# GPS_Tracker_v1_2.net
KiCad netlist of a schematic drawn in EAGLE
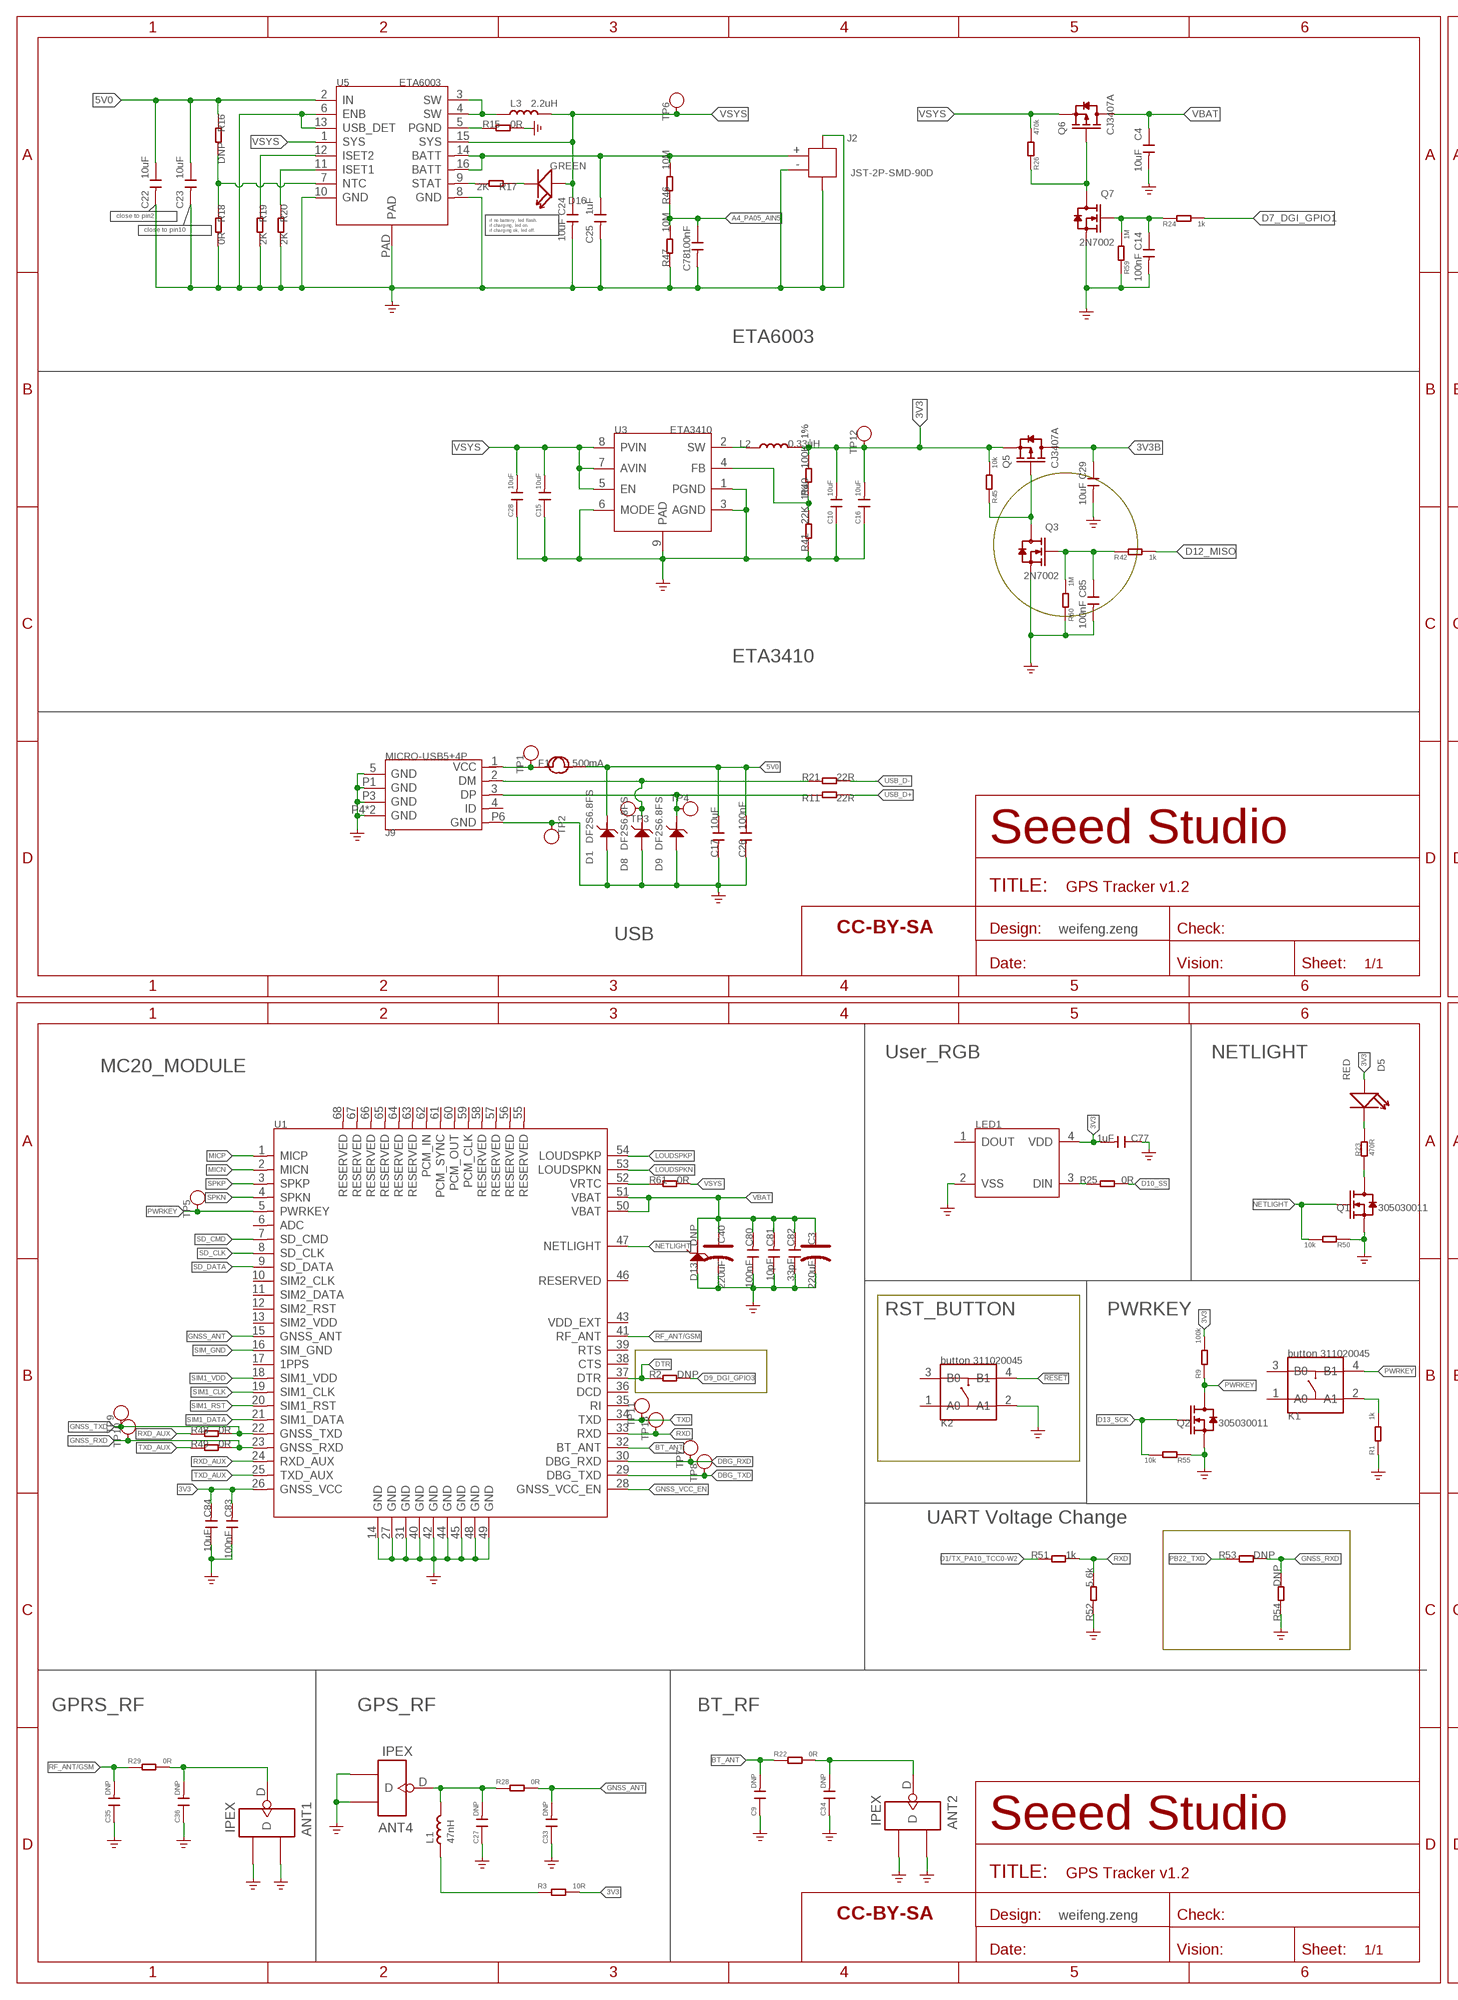
[diagram p0: schematic, sheet 1, part 1 of 2]
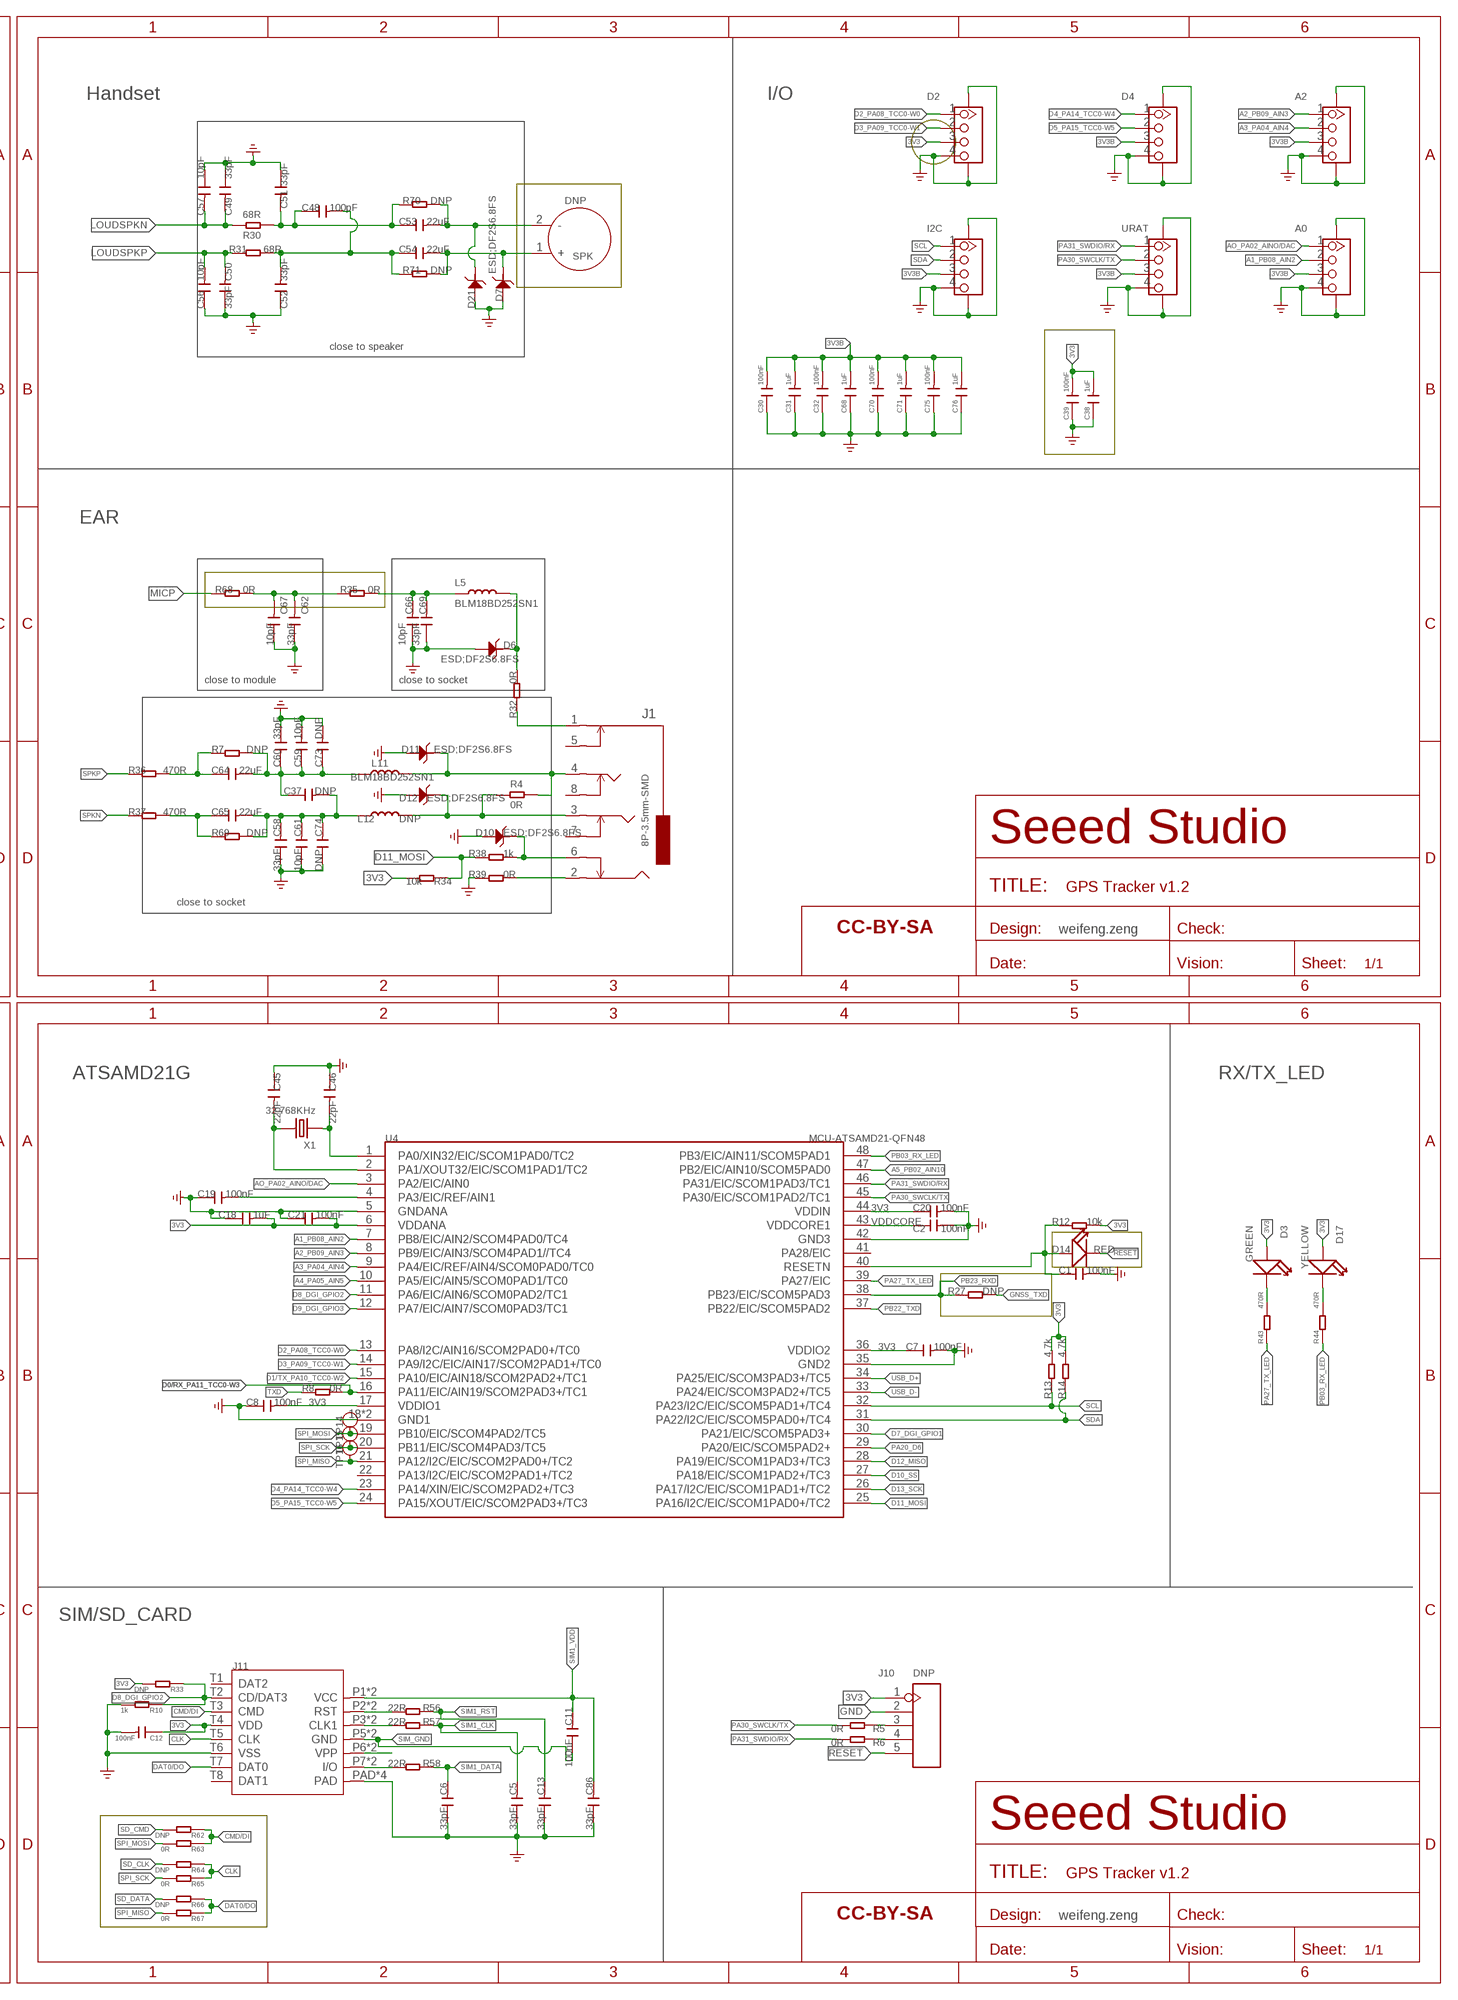
[diagram p1: schematic, sheet 1, part 2 of 2]

(export (version "E")
  (design (tool "Eeschema 10.0.6"))
  (components
    (comp (ref "A0")
      (value "GROVE-CONNECTOR-SMD'90D'")
      (footprint "eagle-import:HW4-SMD-2.0-90D")
      (libsource (lib "eagle-import") (part "GROVE-CONNECTOR-SMD'90D'"))
    )
    (comp (ref "A2")
      (value "GROVE-CONNECTOR-SMD'90D'")
      (footprint "eagle-import:HW4-SMD-2.0-90D")
      (libsource (lib "eagle-import") (part "GROVE-CONNECTOR-SMD'90D'"))
    )
    (comp (ref "ANT1")
      (value "IPEX")
      (footprint "eagle-import:U-FL3P-SMD-2.6X2.6X1.0MM")
      (libsource (lib "eagle-import") (part "ANTENNA-U-FL"))
    )
    (comp (ref "ANT2")
      (value "IPEX")
      (footprint "eagle-import:U-FL3P-SMD-2.6X2.6X1.0MM")
      (libsource (lib "eagle-import") (part "ANTENNA-U-FL"))
    )
    (comp (ref "ANT4")
      (value "IPEX")
      (footprint "eagle-import:U-FL3P-SMD-2.6X2.6X1.0MM")
      (libsource (lib "eagle-import") (part "ANTENNA-U-FL"))
    )
    (comp (ref "C1")
      (value "100nF")
      (footprint "eagle-import:C0402")
      (libsource (lib "eagle-import") (part "C-0402"))
    )
    (comp (ref "C2")
      (value "100nF")
      (footprint "eagle-import:C0402")
      (libsource (lib "eagle-import") (part "C-0402"))
    )
    (comp (ref "C3")
      (value "220uF")
      (footprint "eagle-import:AVX-B")
      (libsource (lib "eagle-import") (part "CAP-POLAR-AVX-B"))
    )
    (comp (ref "C4")
      (value "10uF")
      (footprint "eagle-import:C0603")
      (libsource (lib "eagle-import") (part "C-0603"))
    )
    (comp (ref "C5")
      (value "33pF")
      (footprint "eagle-import:C0402")
      (libsource (lib "eagle-import") (part "C-0402"))
    )
    (comp (ref "C6")
      (value "33pF")
      (footprint "eagle-import:C0402")
      (libsource (lib "eagle-import") (part "C-0402"))
    )
    (comp (ref "C7")
      (value "100nF")
      (footprint "eagle-import:C0402")
      (libsource (lib "eagle-import") (part "C-0402"))
    )
    (comp (ref "C8")
      (value "100nF")
      (footprint "eagle-import:C0402")
      (libsource (lib "eagle-import") (part "C-0402"))
    )
    (comp (ref "C9")
      (value "DNP")
      (footprint "eagle-import:C0402")
      (libsource (lib "eagle-import") (part "C-0402"))
    )
    (comp (ref "C10")
      (value "10uF")
      (footprint "eagle-import:C0603")
      (libsource (lib "eagle-import") (part "C-0603"))
    )
    (comp (ref "C11")
      (value "100nF")
      (footprint "eagle-import:C0402")
      (libsource (lib "eagle-import") (part "C-0402"))
    )
    (comp (ref "C12")
      (value "100nF")
      (footprint "eagle-import:C0402")
      (libsource (lib "eagle-import") (part "C-0402"))
    )
    (comp (ref "C13")
      (value "33pF")
      (footprint "eagle-import:C0402")
      (libsource (lib "eagle-import") (part "C-0402"))
    )
    (comp (ref "C14")
      (value "100nF")
      (footprint "eagle-import:C0603")
      (libsource (lib "eagle-import") (part "C-0603"))
    )
    (comp (ref "C15")
      (value "10uF")
      (footprint "eagle-import:C0603")
      (libsource (lib "eagle-import") (part "C-0603"))
    )
    (comp (ref "C16")
      (value "10uF")
      (footprint "eagle-import:C0603")
      (libsource (lib "eagle-import") (part "C-0603"))
    )
    (comp (ref "C17")
      (value "10uF")
      (footprint "eagle-import:C0603")
      (libsource (lib "eagle-import") (part "C-0603"))
    )
    (comp (ref "C18")
      (value "1uF")
      (footprint "eagle-import:C0402")
      (libsource (lib "eagle-import") (part "C-0402"))
    )
    (comp (ref "C19")
      (value "100nF")
      (footprint "eagle-import:C0402")
      (libsource (lib "eagle-import") (part "C-0402"))
    )
    (comp (ref "C20")
      (value "100nF")
      (footprint "eagle-import:C0402")
      (libsource (lib "eagle-import") (part "C-0402"))
    )
    (comp (ref "C21")
      (value "100nF")
      (footprint "eagle-import:C0402")
      (libsource (lib "eagle-import") (part "C-0402"))
    )
    (comp (ref "C22")
      (value "10uF")
      (footprint "eagle-import:C0603")
      (libsource (lib "eagle-import") (part "C-0603"))
    )
    (comp (ref "C23")
      (value "10uF")
      (footprint "eagle-import:C0603")
      (libsource (lib "eagle-import") (part "C-0603"))
    )
    (comp (ref "C24")
      (value "10uF")
      (footprint "eagle-import:C0603")
      (libsource (lib "eagle-import") (part "C-0603"))
    )
    (comp (ref "C25")
      (value "1uF")
      (footprint "eagle-import:C0402")
      (libsource (lib "eagle-import") (part "C-0402"))
    )
    (comp (ref "C26")
      (value "100nF")
      (footprint "eagle-import:C0402")
      (libsource (lib "eagle-import") (part "C-0402"))
    )
    (comp (ref "C27")
      (value "DNP")
      (footprint "eagle-import:C0402")
      (libsource (lib "eagle-import") (part "C-0402"))
    )
    (comp (ref "C28")
      (value "10uF")
      (footprint "eagle-import:C0603")
      (libsource (lib "eagle-import") (part "C-0603"))
    )
    (comp (ref "C29")
      (value "10uF")
      (footprint "eagle-import:C0603")
      (libsource (lib "eagle-import") (part "C-0603"))
    )
    (comp (ref "C30")
      (value "100nF")
      (footprint "eagle-import:C0402")
      (libsource (lib "eagle-import") (part "C-0402"))
    )
    (comp (ref "C31")
      (value "1uF")
      (footprint "eagle-import:C0402")
      (libsource (lib "eagle-import") (part "C-0402"))
    )
    (comp (ref "C32")
      (value "100nF")
      (footprint "eagle-import:C0402")
      (libsource (lib "eagle-import") (part "C-0402"))
    )
    (comp (ref "C33")
      (value "DNP")
      (footprint "eagle-import:C0402")
      (libsource (lib "eagle-import") (part "C-0402"))
    )
    (comp (ref "C34")
      (value "DNP")
      (footprint "eagle-import:C0402")
      (libsource (lib "eagle-import") (part "C-0402"))
    )
    (comp (ref "C35")
      (value "DNP")
      (footprint "eagle-import:C0402")
      (libsource (lib "eagle-import") (part "C-0402"))
    )
    (comp (ref "C36")
      (value "DNP")
      (footprint "eagle-import:C0402")
      (libsource (lib "eagle-import") (part "C-0402"))
    )
    (comp (ref "C37")
      (value "DNP")
      (footprint "eagle-import:C0402")
      (libsource (lib "eagle-import") (part "C-0402"))
    )
    (comp (ref "C38")
      (value "1uF")
      (footprint "eagle-import:C0402")
      (libsource (lib "eagle-import") (part "C-0402"))
    )
    (comp (ref "C39")
      (value "100nF")
      (footprint "eagle-import:C0402")
      (libsource (lib "eagle-import") (part "C-0402"))
    )
    (comp (ref "C40")
      (value "220uF")
      (footprint "eagle-import:AVX-B")
      (libsource (lib "eagle-import") (part "CAP-POLAR-AVX-B"))
    )
    (comp (ref "C45")
      (value "22pF")
      (footprint "eagle-import:C0402")
      (libsource (lib "eagle-import") (part "C-0402"))
    )
    (comp (ref "C46")
      (value "22pF")
      (footprint "eagle-import:C0402")
      (libsource (lib "eagle-import") (part "C-0402"))
    )
    (comp (ref "C48")
      (value "100pF")
      (footprint "eagle-import:C0402")
      (libsource (lib "eagle-import") (part "C-0402"))
    )
    (comp (ref "C49")
      (value "33pF")
      (footprint "eagle-import:C0402")
      (libsource (lib "eagle-import") (part "C-0402"))
    )
    (comp (ref "C50")
      (value "33pF")
      (footprint "eagle-import:C0402")
      (libsource (lib "eagle-import") (part "C-0402"))
    )
    (comp (ref "C51")
      (value "33pF")
      (footprint "eagle-import:C0402")
      (libsource (lib "eagle-import") (part "C-0402"))
    )
    (comp (ref "C52")
      (value "33pF")
      (footprint "eagle-import:C0402")
      (libsource (lib "eagle-import") (part "C-0402"))
    )
    (comp (ref "C53")
      (value "22uF")
      (footprint "eagle-import:C0805")
      (libsource (lib "eagle-import") (part "CAP-0805"))
    )
    (comp (ref "C54")
      (value "22uF")
      (footprint "eagle-import:C0805")
      (libsource (lib "eagle-import") (part "CAP-0805"))
    )
    (comp (ref "C56")
      (value "10pF")
      (footprint "eagle-import:C0402")
      (libsource (lib "eagle-import") (part "C-0402"))
    )
    (comp (ref "C57")
      (value "10pF")
      (footprint "eagle-import:C0402")
      (libsource (lib "eagle-import") (part "C-0402"))
    )
    (comp (ref "C58")
      (value "33pF")
      (footprint "eagle-import:C0402")
      (libsource (lib "eagle-import") (part "C-0402"))
    )
    (comp (ref "C59")
      (value "10pF")
      (footprint "eagle-import:C0402")
      (libsource (lib "eagle-import") (part "C-0402"))
    )
    (comp (ref "C60")
      (value "33pF")
      (footprint "eagle-import:C0402")
      (libsource (lib "eagle-import") (part "C-0402"))
    )
    (comp (ref "C61")
      (value "10pF")
      (footprint "eagle-import:C0402")
      (libsource (lib "eagle-import") (part "C-0402"))
    )
    (comp (ref "C62")
      (value "33pF")
      (footprint "eagle-import:C0402")
      (libsource (lib "eagle-import") (part "C-0402"))
    )
    (comp (ref "C64")
      (value "22uF")
      (footprint "eagle-import:C0805")
      (libsource (lib "eagle-import") (part "CAP-0805"))
    )
    (comp (ref "C65")
      (value "22uF")
      (footprint "eagle-import:C0805")
      (libsource (lib "eagle-import") (part "CAP-0805"))
    )
    (comp (ref "C66")
      (value "10pF")
      (footprint "eagle-import:C0402")
      (libsource (lib "eagle-import") (part "C-0402"))
    )
    (comp (ref "C67")
      (value "10pF")
      (footprint "eagle-import:C0402")
      (libsource (lib "eagle-import") (part "C-0402"))
    )
    (comp (ref "C68")
      (value "1uF")
      (footprint "eagle-import:C0402")
      (libsource (lib "eagle-import") (part "C-0402"))
    )
    (comp (ref "C69")
      (value "33pF")
      (footprint "eagle-import:C0402")
      (libsource (lib "eagle-import") (part "C-0402"))
    )
    (comp (ref "C70")
      (value "100nF")
      (footprint "eagle-import:C0402")
      (libsource (lib "eagle-import") (part "C-0402"))
    )
    (comp (ref "C71")
      (value "1uF")
      (footprint "eagle-import:C0402")
      (libsource (lib "eagle-import") (part "C-0402"))
    )
    (comp (ref "C73")
      (value "DNP")
      (footprint "eagle-import:C0402")
      (libsource (lib "eagle-import") (part "C-0402"))
    )
    (comp (ref "C74")
      (value "DNP")
      (footprint "eagle-import:C0402")
      (libsource (lib "eagle-import") (part "C-0402"))
    )
    (comp (ref "C75")
      (value "100nF")
      (footprint "eagle-import:C0402")
      (libsource (lib "eagle-import") (part "C-0402"))
    )
    (comp (ref "C76")
      (value "1uF")
      (footprint "eagle-import:C0402")
      (libsource (lib "eagle-import") (part "C-0402"))
    )
    (comp (ref "C77")
      (value "1uF")
      (footprint "eagle-import:C0402")
      (libsource (lib "eagle-import") (part "C-0402"))
    )
    (comp (ref "C78")
      (value "100nF")
      (footprint "eagle-import:C0402")
      (libsource (lib "eagle-import") (part "C-0402"))
    )
    (comp (ref "C80")
      (value "100nF")
      (footprint "eagle-import:C0402")
      (libsource (lib "eagle-import") (part "C-0402"))
    )
    (comp (ref "C81")
      (value "10pF")
      (footprint "eagle-import:C0402")
      (libsource (lib "eagle-import") (part "C-0402"))
    )
    (comp (ref "C82")
      (value "33pF")
      (footprint "eagle-import:C0402")
      (libsource (lib "eagle-import") (part "C-0402"))
    )
    (comp (ref "C83")
      (value "100nF")
      (footprint "eagle-import:C0402")
      (libsource (lib "eagle-import") (part "C-0402"))
    )
    (comp (ref "C84")
      (value "10uF")
      (footprint "eagle-import:C0603")
      (libsource (lib "eagle-import") (part "C-0603"))
    )
    (comp (ref "C85")
      (value "100nF")
      (footprint "eagle-import:C0603")
      (libsource (lib "eagle-import") (part "C-0603"))
    )
    (comp (ref "C86")
      (value "33pF")
      (footprint "eagle-import:C0402")
      (libsource (lib "eagle-import") (part "C-0402"))
    )
    (comp (ref "D1")
      (value "DF2S6.8FS")
      (footprint "eagle-import:SOD-923")
      (libsource (lib "eagle-import") (part "D-ESD-2P'DF2S6.8FS'"))
    )
    (comp (ref "D2")
      (value "GROVE-CONNECTOR-SMD'90D'")
      (footprint "eagle-import:HW4-SMD-2.0-90D")
      (libsource (lib "eagle-import") (part "GROVE-CONNECTOR-SMD'90D'"))
    )
    (comp (ref "D3")
      (value "GREEN")
      (footprint "eagle-import:LED-0402")
      (libsource (lib "eagle-import") (part "LED-0402"))
    )
    (comp (ref "D4")
      (value "GROVE-CONNECTOR-SMD'90D'")
      (footprint "eagle-import:HW4-SMD-2.0-90D")
      (libsource (lib "eagle-import") (part "GROVE-CONNECTOR-SMD'90D'"))
    )
    (comp (ref "D5")
      (value "RED")
      (footprint "eagle-import:LED-0402")
      (libsource (lib "eagle-import") (part "LED-0402"))
    )
    (comp (ref "D6")
      (value "ESD;DF2S6.8FS")
      (footprint "eagle-import:SOD-923")
      (libsource (lib "eagle-import") (part "D-ESD-2P'DF2S6.8FS'"))
    )
    (comp (ref "D7")
      (value "ESD;DF2S6.8FS")
      (footprint "eagle-import:SOD-923")
      (libsource (lib "eagle-import") (part "D-ESD-2P'DF2S6.8FS'"))
    )
    (comp (ref "D8")
      (value "DF2S6.8FS")
      (footprint "eagle-import:SOD-923")
      (libsource (lib "eagle-import") (part "D-ESD-2P'DF2S6.8FS'"))
    )
    (comp (ref "D9")
      (value "DF2S6.8FS")
      (footprint "eagle-import:SOD-923")
      (libsource (lib "eagle-import") (part "D-ESD-2P'DF2S6.8FS'"))
    )
    (comp (ref "D10")
      (value "ESD;DF2S6.8FS")
      (footprint "eagle-import:SOD-923")
      (libsource (lib "eagle-import") (part "D-ESD-2P'DF2S6.8FS'"))
    )
    (comp (ref "D11")
      (value "ESD;DF2S6.8FS")
      (footprint "eagle-import:SOD-923")
      (libsource (lib "eagle-import") (part "D-ESD-2P'DF2S6.8FS'"))
    )
    (comp (ref "D12")
      (value "ESD;DF2S6.8FS")
      (footprint "eagle-import:SOD-923")
      (libsource (lib "eagle-import") (part "D-ESD-2P'DF2S6.8FS'"))
    )
    (comp (ref "D13")
      (value "DNP")
      (footprint "eagle-import:SOD-923")
      (libsource (lib "eagle-import") (part "D-ESD-2P'DF2S6.8FS'"))
    )
    (comp (ref "D14")
      (value "RED")
      (footprint "eagle-import:LED-0402")
      (libsource (lib "eagle-import") (part "LED-0402"))
    )
    (comp (ref "D16")
      (value "GREEN")
      (footprint "eagle-import:LED-0402")
      (libsource (lib "eagle-import") (part "LED-0402"))
    )
    (comp (ref "D17")
      (value "YELLOW")
      (footprint "eagle-import:LED-0402")
      (libsource (lib "eagle-import") (part "LED-0402"))
    )
    (comp (ref "D21")
      (value "ESD;DF2S6.8FS")
      (footprint "eagle-import:SOD-923")
      (libsource (lib "eagle-import") (part "D-ESD-2P'DF2S6.8FS'"))
    )
    (comp (ref "F1")
      (value "500mA")
      (footprint "eagle-import:F1206")
      (libsource (lib "eagle-import") (part "FUSE'1206'"))
    )
    (comp (ref "FR1")
      (value "SEEEDSTUDIO-OPEN-SCH-FRAME")
      (footprint "eagle-import:SEEEDSTUDIO-PCB-FRAME")
      (libsource (lib "eagle-import") (part "SEEEDSTUDIO-OPEN-SCH-FRAME"))
    )
    (comp (ref "FR2")
      (value "SEEEDSTUDIO-OPEN-SCH-FRAME")
      (footprint "eagle-import:SEEEDSTUDIO-PCB-FRAME")
      (libsource (lib "eagle-import") (part "SEEEDSTUDIO-OPEN-SCH-FRAME"))
    )
    (comp (ref "FR3")
      (value "SEEEDSTUDIO-OPEN-SCH-FRAME")
      (footprint "eagle-import:SEEEDSTUDIO-PCB-FRAME")
      (libsource (lib "eagle-import") (part "SEEEDSTUDIO-OPEN-SCH-FRAME"))
    )
    (comp (ref "FR4")
      (value "SEEEDSTUDIO-OPEN-SCH-FRAME")
      (footprint "eagle-import:SEEEDSTUDIO-PCB-FRAME")
      (libsource (lib "eagle-import") (part "SEEEDSTUDIO-OPEN-SCH-FRAME"))
    )
    (comp (ref "I2C")
      (value "GROVE-CONNECTOR-SMD'90D'")
      (footprint "eagle-import:HW4-SMD-2.0-90D")
      (libsource (lib "eagle-import") (part "GROVE-CONNECTOR-SMD'90D'"))
    )
    (comp (ref "J1")
      (value "8P-3.5mm-SMD")
      (footprint "eagle-import:8P-3.5-SMD")
      (libsource (lib "eagle-import") (part "AUDIO-8P'PJ-3536-L6S'"))
    )
    (comp (ref "J2")
      (value "JST-2P-SMD-90D")
      (footprint "eagle-import:HW2-SMD-1.0-90D")
      (libsource (lib "eagle-import") (part "JST-2P-SMD'1.0'"))
    )
    (comp (ref "J9")
      (value "MICRO-USB5+4P")
      (footprint "eagle-import:MICRO-USB5+5P-SMD-0.65-7.2X5.06MM")
      (libsource (lib "eagle-import") (part "MICRO-USB5+4P"))
    )
    (comp (ref "J10")
      (value "DNP")
      (footprint "eagle-import:H5-SMD-2.0-TEST")
      (libsource (lib "eagle-import") (part "HEADER-5P-TEST"))
    )
    (comp (ref "J11")
      (value "NANO_SIM+TF-24P")
      (footprint "eagle-import:SIM+TF-24P-SMD-1.2-15.05X13.66X2.5MM")
      (libsource (lib "eagle-import") (part "NANO_SIM+TF-24P"))
    )
    (comp (ref "K1")
      (value "button 311020045")
      (footprint "eagle-import:SW4P-SMD-4.5X3.2X2.5MM")
      (libsource (lib "eagle-import") (part "BUTTON-4P-4.5X3.2"))
    )
    (comp (ref "K2")
      (value "button 311020045")
      (footprint "eagle-import:SW4P-SMD-4.5X3.2X2.5MM")
      (libsource (lib "eagle-import") (part "BUTTON-4P-4.5X3.2"))
    )
    (comp (ref "L1")
      (value "47nH")
      (footprint "eagle-import:L0402")
      (libsource (lib "eagle-import") (part "INDUCTOR/FERRITE-BEAD'0402'"))
    )
    (comp (ref "L2")
      (value "0.33uH")
      (footprint "eagle-import:L201610")
      (libsource (lib "eagle-import") (part "L-MPM201610SR33_T"))
    )
    (comp (ref "L3")
      (value "2.2uH")
      (footprint "eagle-import:L0805")
      (libsource (lib "eagle-import") (part "INDUCTOR/FERRITE-BEAD'0805'"))
    )
    (comp (ref "L5")
      (value "BLM18BD252SN1")
      (footprint "eagle-import:L0603")
      (libsource (lib "eagle-import") (part "L'0603'"))
    )
    (comp (ref "L11")
      (value "BLM18BD252SN1")
      (footprint "eagle-import:L0603")
      (libsource (lib "eagle-import") (part "L'0603'"))
    )
    (comp (ref "L12")
      (value "DNP")
      (footprint "eagle-import:L0603")
      (libsource (lib "eagle-import") (part "L'0603'"))
    )
    (comp (ref "LED1")
      (value "LED-RGB-4P-SK6812-SK6812")
      (footprint "eagle-import:LED4-1.75-3.7X3.5X0.95MM")
      (libsource (lib "eagle-import") (part "LED-RGB-4P-SK6812-SK6812"))
    )
    (comp (ref "Q1")
      (value "305030011")
      (footprint "eagle-import:SOT-323")
      (libsource (lib "eagle-import") (part "MOSFET-N+'SI1304BDL'"))
    )
    (comp (ref "Q2")
      (value "305030011")
      (footprint "eagle-import:SOT-323")
      (libsource (lib "eagle-import") (part "MOSFET-N+'SI1304BDL'"))
    )
    (comp (ref "Q3")
      (value "2N7002")
      (footprint "eagle-import:SOT-23")
      (libsource (lib "eagle-import") (part "MOSFET-N+'SOT23'"))
    )
    (comp (ref "Q5")
      (value "CJ3407A")
      (footprint "eagle-import:SOT-23")
      (libsource (lib "eagle-import") (part "MOSFET-P'SI2323CDS/SI2305DS{lt}BR{gt}'"))
    )
    (comp (ref "Q6")
      (value "CJ3407A")
      (footprint "eagle-import:SOT-23")
      (libsource (lib "eagle-import") (part "MOSFET-P'SI2323CDS/SI2305DS{lt}BR{gt}'"))
    )
    (comp (ref "Q7")
      (value "2N7002")
      (footprint "eagle-import:SOT-23")
      (libsource (lib "eagle-import") (part "MOSFET-N+'SOT23'"))
    )
    (comp (ref "R1")
      (value "1k")
      (footprint "eagle-import:R0402")
      (libsource (lib "eagle-import") (part "R-0402"))
    )
    (comp (ref "R2")
      (value "DNP")
      (footprint "eagle-import:R0402")
      (libsource (lib "eagle-import") (part "R-0402"))
    )
    (comp (ref "R3")
      (value "10R")
      (footprint "eagle-import:R0402")
      (libsource (lib "eagle-import") (part "R-0402"))
    )
    (comp (ref "R4")
      (value "0R")
      (footprint "eagle-import:R0402")
      (libsource (lib "eagle-import") (part "R-0402"))
    )
    (comp (ref "R5")
      (value "0R")
      (footprint "eagle-import:R0402")
      (libsource (lib "eagle-import") (part "R-0402"))
    )
    (comp (ref "R6")
      (value "0R")
      (footprint "eagle-import:R0402")
      (libsource (lib "eagle-import") (part "R-0402"))
    )
    (comp (ref "R7")
      (value "DNP")
      (footprint "eagle-import:R0402")
      (libsource (lib "eagle-import") (part "R-0402"))
    )
    (comp (ref "R8")
      (value "0R")
      (footprint "eagle-import:R0402")
      (libsource (lib "eagle-import") (part "R-0402"))
    )
    (comp (ref "R9")
      (value "100k")
      (footprint "eagle-import:R0402")
      (libsource (lib "eagle-import") (part "R-0402"))
    )
    (comp (ref "R10")
      (value "1k")
      (footprint "eagle-import:R0402")
      (libsource (lib "eagle-import") (part "R-0402"))
    )
    (comp (ref "R11")
      (value "22R")
      (footprint "eagle-import:R0402")
      (libsource (lib "eagle-import") (part "R-0402"))
    )
    (comp (ref "R12")
      (value "10k")
      (footprint "eagle-import:R0402")
      (libsource (lib "eagle-import") (part "R-0402"))
    )
    (comp (ref "R13")
      (value "4.7k")
      (footprint "eagle-import:R0402")
      (libsource (lib "eagle-import") (part "R-0402"))
    )
    (comp (ref "R14")
      (value "4.7k")
      (footprint "eagle-import:R0402")
      (libsource (lib "eagle-import") (part "R-0402"))
    )
    (comp (ref "R15")
      (value "0R")
      (footprint "eagle-import:R0402")
      (libsource (lib "eagle-import") (part "R-0402"))
    )
    (comp (ref "R16")
      (value "DNP")
      (footprint "eagle-import:R0402")
      (libsource (lib "eagle-import") (part "R-0402"))
    )
    (comp (ref "R17")
      (value "2K")
      (footprint "eagle-import:R0402")
      (libsource (lib "eagle-import") (part "R-0402"))
    )
    (comp (ref "R18")
      (value "0R")
      (footprint "eagle-import:R0402")
      (libsource (lib "eagle-import") (part "R-0402"))
    )
    (comp (ref "R19")
      (value "2K")
      (footprint "eagle-import:R0402")
      (libsource (lib "eagle-import") (part "R-0402"))
    )
    (comp (ref "R20")
      (value "2K")
      (footprint "eagle-import:R0402")
      (libsource (lib "eagle-import") (part "R-0402"))
    )
    (comp (ref "R21")
      (value "22R")
      (footprint "eagle-import:R0402")
      (libsource (lib "eagle-import") (part "R-0402"))
    )
    (comp (ref "R22")
      (value "0R")
      (footprint "eagle-import:R0402")
      (libsource (lib "eagle-import") (part "R-0402"))
    )
    (comp (ref "R23")
      (value "470R")
      (footprint "eagle-import:R0402")
      (libsource (lib "eagle-import") (part "R-0402"))
    )
    (comp (ref "R24")
      (value "1k")
      (footprint "eagle-import:R0402")
      (libsource (lib "eagle-import") (part "R-0402"))
    )
    (comp (ref "R25")
      (value "0R")
      (footprint "eagle-import:R0402")
      (libsource (lib "eagle-import") (part "R-0402"))
    )
    (comp (ref "R26")
      (value "470k")
      (footprint "eagle-import:R0402")
      (libsource (lib "eagle-import") (part "R-0402"))
    )
    (comp (ref "R27")
      (value "DNP")
      (footprint "eagle-import:R0402")
      (libsource (lib "eagle-import") (part "R-0402"))
    )
    (comp (ref "R28")
      (value "0R")
      (footprint "eagle-import:R0402")
      (libsource (lib "eagle-import") (part "R-0402"))
    )
    (comp (ref "R29")
      (value "0R")
      (footprint "eagle-import:R0402")
      (libsource (lib "eagle-import") (part "R-0402"))
    )
    (comp (ref "R30")
      (value "68R")
      (footprint "eagle-import:R0402")
      (libsource (lib "eagle-import") (part "R-0402"))
    )
    (comp (ref "R31")
      (value "68R")
      (footprint "eagle-import:R0402")
      (libsource (lib "eagle-import") (part "R-0402"))
    )
    (comp (ref "R32")
      (value "0R")
      (footprint "eagle-import:R0402")
      (libsource (lib "eagle-import") (part "R-0402"))
    )
    (comp (ref "R33")
      (value "DNP")
      (footprint "eagle-import:R0402")
      (libsource (lib "eagle-import") (part "R-0402"))
    )
    (comp (ref "R34")
      (value "10k")
      (footprint "eagle-import:R0402")
      (libsource (lib "eagle-import") (part "R-0402"))
    )
    (comp (ref "R35")
      (value "0R")
      (footprint "eagle-import:R0402")
      (libsource (lib "eagle-import") (part "R-0402"))
    )
    (comp (ref "R36")
      (value "470R")
      (footprint "eagle-import:R0402")
      (libsource (lib "eagle-import") (part "R-0402"))
    )
    (comp (ref "R37")
      (value "470R")
      (footprint "eagle-import:R0402")
      (libsource (lib "eagle-import") (part "R-0402"))
    )
    (comp (ref "R38")
      (value "1k")
      (footprint "eagle-import:R0402")
      (libsource (lib "eagle-import") (part "R-0402"))
    )
    (comp (ref "R39")
      (value "0R")
      (footprint "eagle-import:R0402")
      (libsource (lib "eagle-import") (part "R-0402"))
    )
    (comp (ref "R40")
      (value "100K_1%")
      (footprint "eagle-import:R0402")
      (libsource (lib "eagle-import") (part "R-0402"))
    )
    (comp (ref "R41")
      (value "22K_1%")
      (footprint "eagle-import:R0402")
      (libsource (lib "eagle-import") (part "R-0402"))
    )
    (comp (ref "R42")
      (value "1k")
      (footprint "eagle-import:R0402")
      (libsource (lib "eagle-import") (part "R-0402"))
    )
    (comp (ref "R43")
      (value "470R")
      (footprint "eagle-import:R0402")
      (libsource (lib "eagle-import") (part "R-0402"))
    )
    (comp (ref "R44")
      (value "470R")
      (footprint "eagle-import:R0402")
      (libsource (lib "eagle-import") (part "R-0402"))
    )
    (comp (ref "R45")
      (value "10k")
      (footprint "eagle-import:R0402")
      (libsource (lib "eagle-import") (part "R-0402"))
    )
    (comp (ref "R46")
      (value "10M")
      (footprint "eagle-import:R0402")
      (libsource (lib "eagle-import") (part "R-0402"))
    )
    (comp (ref "R47")
      (value "10M")
      (footprint "eagle-import:R0402")
      (libsource (lib "eagle-import") (part "R-0402"))
    )
    (comp (ref "R48")
      (value "0R")
      (footprint "eagle-import:R0402")
      (libsource (lib "eagle-import") (part "R-0402"))
    )
    (comp (ref "R49")
      (value "0R")
      (footprint "eagle-import:R0402")
      (libsource (lib "eagle-import") (part "R-0402"))
    )
    (comp (ref "R50")
      (value "10k")
      (footprint "eagle-import:R0402")
      (libsource (lib "eagle-import") (part "R-0402"))
    )
    (comp (ref "R51")
      (value "1k")
      (footprint "eagle-import:R0402")
      (libsource (lib "eagle-import") (part "R-0402"))
    )
    (comp (ref "R52")
      (value "5.6k")
      (footprint "eagle-import:R0402")
      (libsource (lib "eagle-import") (part "R-0402"))
    )
    (comp (ref "R53")
      (value "DNP")
      (footprint "eagle-import:R0402")
      (libsource (lib "eagle-import") (part "R-0402"))
    )
    (comp (ref "R54")
      (value "DNP")
      (footprint "eagle-import:R0402")
      (libsource (lib "eagle-import") (part "R-0402"))
    )
    (comp (ref "R55")
      (value "10k")
      (footprint "eagle-import:R0402")
      (libsource (lib "eagle-import") (part "R-0402"))
    )
    (comp (ref "R56")
      (value "22R")
      (footprint "eagle-import:R0402")
      (libsource (lib "eagle-import") (part "R-0402"))
    )
    (comp (ref "R57")
      (value "22R")
      (footprint "eagle-import:R0402")
      (libsource (lib "eagle-import") (part "R-0402"))
    )
    (comp (ref "R58")
      (value "22R")
      (footprint "eagle-import:R0402")
      (libsource (lib "eagle-import") (part "R-0402"))
    )
    (comp (ref "R59")
      (value "1M")
      (footprint "eagle-import:R0402")
      (libsource (lib "eagle-import") (part "R-0402"))
    )
    (comp (ref "R60")
      (value "1M")
      (footprint "eagle-import:R0402")
      (libsource (lib "eagle-import") (part "R-0402"))
    )
    (comp (ref "R61")
      (value "0R")
      (footprint "eagle-import:R0603")
      (libsource (lib "eagle-import") (part "R-0603"))
    )
    (comp (ref "R62")
      (value "DNP")
      (footprint "eagle-import:R0402")
      (libsource (lib "eagle-import") (part "R-0402"))
    )
    (comp (ref "R63")
      (value "0R")
      (footprint "eagle-import:R0402")
      (libsource (lib "eagle-import") (part "R-0402"))
    )
    (comp (ref "R64")
      (value "DNP")
      (footprint "eagle-import:R0402")
      (libsource (lib "eagle-import") (part "R-0402"))
    )
    (comp (ref "R65")
      (value "0R")
      (footprint "eagle-import:R0402")
      (libsource (lib "eagle-import") (part "R-0402"))
    )
    (comp (ref "R66")
      (value "DNP")
      (footprint "eagle-import:R0402")
      (libsource (lib "eagle-import") (part "R-0402"))
    )
    (comp (ref "R67")
      (value "0R")
      (footprint "eagle-import:R0402")
      (libsource (lib "eagle-import") (part "R-0402"))
    )
    (comp (ref "R68")
      (value "0R")
      (footprint "eagle-import:R0402")
      (libsource (lib "eagle-import") (part "R-0402"))
    )
    (comp (ref "R69")
      (value "DNP")
      (footprint "eagle-import:R0402")
      (libsource (lib "eagle-import") (part "R-0402"))
    )
    (comp (ref "R70")
      (value "DNP")
      (footprint "eagle-import:R0402")
      (libsource (lib "eagle-import") (part "R-0402"))
    )
    (comp (ref "R71")
      (value "DNP")
      (footprint "eagle-import:R0402")
      (libsource (lib "eagle-import") (part "R-0402"))
    )
    (comp (ref "SPK")
      (value "DNP")
      (footprint "eagle-import:2P-SMD-SPEAKER")
      (libsource (lib "eagle-import") (part "SPEAKER"))
    )
    (comp (ref "TP1")
      (value "TEST-POINT'4545'")
      (footprint "eagle-import:TP-D45MIL")
      (fields (field (name "PARTNO") "DNP"))
      (libsource (lib "eagle-import") (part "TEST-POINT'4545'"))
    )
    (comp (ref "TP2")
      (value "TEST-POINT'4545'")
      (footprint "eagle-import:TP-D45MIL")
      (fields (field (name "PARTNO") "DNP"))
      (libsource (lib "eagle-import") (part "TEST-POINT'4545'"))
    )
    (comp (ref "TP3")
      (value "TEST-POINT'4545'")
      (footprint "eagle-import:TP-D45MIL")
      (fields (field (name "PARTNO") "DNP"))
      (libsource (lib "eagle-import") (part "TEST-POINT'4545'"))
    )
    (comp (ref "TP4")
      (value "TEST-POINT'4545'")
      (footprint "eagle-import:TP-D45MIL")
      (fields (field (name "PARTNO") "DNP"))
      (libsource (lib "eagle-import") (part "TEST-POINT'4545'"))
    )
    (comp (ref "TP5")
      (value "TEST-POINT'4545'")
      (footprint "eagle-import:TP-D45MIL")
      (fields (field (name "PARTNO") "DNP"))
      (libsource (lib "eagle-import") (part "TEST-POINT'4545'"))
    )
    (comp (ref "TP6")
      (value "TEST-POINT'4545'")
      (footprint "eagle-import:TP-D45MIL")
      (fields (field (name "PARTNO") "DNP"))
      (libsource (lib "eagle-import") (part "TEST-POINT'4545'"))
    )
    (comp (ref "TP7")
      (value "TEST-POINT'4545'")
      (footprint "eagle-import:TP-D45MIL")
      (fields (field (name "PARTNO") "DNP"))
      (libsource (lib "eagle-import") (part "TEST-POINT'4545'"))
    )
    (comp (ref "TP8")
      (value "TEST-POINT'4545'")
      (footprint "eagle-import:TP-D45MIL")
      (fields (field (name "PARTNO") "DNP"))
      (libsource (lib "eagle-import") (part "TEST-POINT'4545'"))
    )
    (comp (ref "TP9")
      (value "TEST-POINT'4545'")
      (footprint "eagle-import:TP-D45MIL")
      (fields (field (name "PARTNO") "DNP"))
      (libsource (lib "eagle-import") (part "TEST-POINT'4545'"))
    )
    (comp (ref "TP10")
      (value "TEST-POINT'4545'")
      (footprint "eagle-import:TP-D45MIL")
      (fields (field (name "PARTNO") "DNP"))
      (libsource (lib "eagle-import") (part "TEST-POINT'4545'"))
    )
    (comp (ref "TP11")
      (value "TEST-POINT'4545'")
      (footprint "eagle-import:TP-D45MIL")
      (fields (field (name "PARTNO") "DNP"))
      (libsource (lib "eagle-import") (part "TEST-POINT'4545'"))
    )
    (comp (ref "TP12")
      (value "TEST-POINT'4545'")
      (footprint "eagle-import:TP-D45MIL")
      (fields (field (name "PARTNO") "DNP"))
      (libsource (lib "eagle-import") (part "TEST-POINT'4545'"))
    )
    (comp (ref "TP13")
      (value "TEST-POINT'4545'")
      (footprint "eagle-import:TP-D45MIL")
      (fields (field (name "PARTNO") "DNP"))
      (libsource (lib "eagle-import") (part "TEST-POINT'4545'"))
    )
    (comp (ref "TP14")
      (value "TEST-POINT'4545'")
      (footprint "eagle-import:TP-D45MIL")
      (fields (field (name "PARTNO") "DNP"))
      (libsource (lib "eagle-import") (part "TEST-POINT'4545'"))
    )
    (comp (ref "TP15")
      (value "TEST-POINT'4545'")
      (footprint "eagle-import:TP-D45MIL")
      (fields (field (name "PARTNO") "DNP"))
      (libsource (lib "eagle-import") (part "TEST-POINT'4545'"))
    )
    (comp (ref "TP16")
      (value "TEST-POINT'4545'")
      (footprint "eagle-import:TP-D45MIL")
      (fields (field (name "PARTNO") "DNP"))
      (libsource (lib "eagle-import") (part "TEST-POINT'4545'"))
    )
    (comp (ref "U1")
      (value "MODULE-MC20")
      (footprint "eagle-import:MODULE68P-SMD-1.0-18.7X16X2.1MM")
      (libsource (lib "eagle-import") (part "MODULE-MC20"))
    )
    (comp (ref "U3")
      (value "ETA3410")
      (footprint "eagle-import:DFN8G-0.5-2X2MM")
      (libsource (lib "eagle-import") (part "CONVERTER-ETA3410"))
    )
    (comp (ref "U4")
      (value "MCU-ATSAMD21-QFN48")
      (footprint "eagle-import:QFN48-7X7")
      (libsource (lib "eagle-import") (part "MCU-ATSAMD21-QFN48"))
    )
    (comp (ref "U5")
      (value "ETA6003")
      (footprint "eagle-import:QFN16G-0.5-3X3MM@1")
      (libsource (lib "eagle-import") (part "PMIC-ETA6003"))
    )
    (comp (ref "URAT")
      (value "GROVE-CONNECTOR-SMD'90D'")
      (footprint "eagle-import:HW4-SMD-2.0-90D")
      (libsource (lib "eagle-import") (part "GROVE-CONNECTOR-SMD'90D'"))
    )
    (comp (ref "X1")
      (value "32.768KHz")
      (footprint "eagle-import:X2-SMD-L2.0X1.2X0.55MM")
      (libsource (lib "eagle-import") (part "CRYSTAL-2P'NX2012SA'"))
    )
  )
  (nets
    (net (code "1") (name "/VDDCORE") (class "Default")
      (node (ref "C2") (pin "1") (pinfunction "1_1") (pintype "passive"))
      (node (ref "U4") (pin "43") (pinfunction "VDDCORE1_43") (pintype "input"))
    )
    (net (code "2") (name "/~{RESET}") (class "Default")
      (node (ref "D14") (pin "-") (pinfunction "-_-") (pintype "passive"))
      (node (ref "J10") (pin "5") (pinfunction "5_5") (pintype "bidirectional"))
      (node (ref "K2") (pin "4") (pinfunction "B1_4") (pintype "bidirectional"))
    )
    (net (code "3") (name "3V3") (class "Default")
      (node (ref "C10") (pin "2") (pinfunction "2_2") (pintype "passive"))
      (node (ref "C12") (pin "1") (pinfunction "1_1") (pintype "passive"))
      (node (ref "C16") (pin "2") (pinfunction "2_2") (pintype "passive"))
      (node (ref "C18") (pin "2") (pinfunction "2_2") (pintype "passive"))
      (node (ref "C20") (pin "1") (pinfunction "1_1") (pintype "passive"))
      (node (ref "C21") (pin "2") (pinfunction "2_2") (pintype "passive"))
      (node (ref "C38") (pin "2") (pinfunction "2_2") (pintype "passive"))
      (node (ref "C39") (pin "2") (pinfunction "2_2") (pintype "passive"))
      (node (ref "C7") (pin "1") (pinfunction "1_1") (pintype "passive"))
      (node (ref "C77") (pin "2") (pinfunction "2_2") (pintype "passive"))
      (node (ref "C8") (pin "2") (pinfunction "2_2") (pintype "passive"))
      (node (ref "C83") (pin "2") (pinfunction "2_2") (pintype "passive"))
      (node (ref "C84") (pin "2") (pinfunction "2_2") (pintype "passive"))
      (node (ref "D17") (pin "+") (pinfunction "+_+") (pintype "passive"))
      (node (ref "D2") (pin "3") (pinfunction "3_3") (pintype "bidirectional"))
      (node (ref "D3") (pin "+") (pinfunction "+_+") (pintype "passive"))
      (node (ref "D5") (pin "+") (pinfunction "+_+") (pintype "passive"))
      (node (ref "J10") (pin "1") (pinfunction "1_1") (pintype "bidirectional"))
      (node (ref "J11") (pin "T4") (pinfunction "VDD_T4") (pintype "bidirectional"))
      (node (ref "L2") (pin "2") (pinfunction "2_2") (pintype "passive"))
      (node (ref "LED1") (pin "4") (pinfunction "VDD_4") (pintype "bidirectional"))
      (node (ref "Q5") (pin "2") (pinfunction "S_2") (pintype "passive"))
      (node (ref "R12") (pin "1") (pinfunction "1_1") (pintype "passive"))
      (node (ref "R13") (pin "2") (pinfunction "2_2") (pintype "passive"))
      (node (ref "R14") (pin "2") (pinfunction "2_2") (pintype "passive"))
      (node (ref "R3") (pin "2") (pinfunction "2_2") (pintype "passive"))
      (node (ref "R33") (pin "2") (pinfunction "2_2") (pintype "passive"))
      (node (ref "R34") (pin "1") (pinfunction "1_1") (pintype "passive"))
      (node (ref "R40") (pin "2") (pinfunction "2_2") (pintype "passive"))
      (node (ref "R45") (pin "2") (pinfunction "2_2") (pintype "passive"))
      (node (ref "R9") (pin "2") (pinfunction "2_2") (pintype "passive"))
      (node (ref "TP12") (pin "T") (pinfunction "T_T") (pintype "bidirectional"))
      (node (ref "U1") (pin "26") (pinfunction "GNSS_VCC_26") (pintype "bidirectional"))
      (node (ref "U4") (pin "17") (pinfunction "VDDIO1_17") (pintype "power_in"))
      (node (ref "U4") (pin "36") (pinfunction "VDDIO2_36") (pintype "power_in"))
      (node (ref "U4") (pin "44") (pinfunction "VDDIN_44") (pintype "power_in"))
      (node (ref "U4") (pin "6") (pinfunction "VDDANA_6") (pintype "power_in"))
    )
    (net (code "4") (name "3V3B") (class "Default")
      (node (ref "A0") (pin "3") (pinfunction "3_3") (pintype "bidirectional"))
      (node (ref "A2") (pin "3") (pinfunction "3_3") (pintype "bidirectional"))
      (node (ref "C29") (pin "1") (pinfunction "1_1") (pintype "passive"))
      (node (ref "C30") (pin "2") (pinfunction "2_2") (pintype "passive"))
      (node (ref "C31") (pin "2") (pinfunction "2_2") (pintype "passive"))
      (node (ref "C32") (pin "2") (pinfunction "2_2") (pintype "passive"))
      (node (ref "C68") (pin "2") (pinfunction "2_2") (pintype "passive"))
      (node (ref "C70") (pin "2") (pinfunction "2_2") (pintype "passive"))
      (node (ref "C71") (pin "2") (pinfunction "2_2") (pintype "passive"))
      (node (ref "C75") (pin "2") (pinfunction "2_2") (pintype "passive"))
      (node (ref "C76") (pin "2") (pinfunction "2_2") (pintype "passive"))
      (node (ref "D4") (pin "3") (pinfunction "3_3") (pintype "bidirectional"))
      (node (ref "I2C") (pin "3") (pinfunction "3_3") (pintype "bidirectional"))
      (node (ref "Q5") (pin "3") (pinfunction "D_3") (pintype "passive"))
      (node (ref "URAT") (pin "3") (pinfunction "3_3") (pintype "bidirectional"))
    )
    (net (code "5") (name "5V0") (class "Default")
      (node (ref "C17") (pin "1") (pinfunction "1_1") (pintype "passive"))
      (node (ref "C22") (pin "1") (pinfunction "1_1") (pintype "passive"))
      (node (ref "C23") (pin "1") (pinfunction "1_1") (pintype "passive"))
      (node (ref "C26") (pin "1") (pinfunction "1_1") (pintype "passive"))
      (node (ref "D1") (pin "1") (pinfunction "2_1") (pintype "bidirectional"))
      (node (ref "F1") (pin "2") (pinfunction "2_2") (pintype "bidirectional"))
      (node (ref "R16") (pin "1") (pinfunction "1_1") (pintype "passive"))
      (node (ref "U5") (pin "2") (pinfunction "IN_2") (pintype "bidirectional"))
    )
    (net (code "6") (name "A1_PB08_AIN2") (class "Default")
      (node (ref "A0") (pin "2") (pinfunction "2_2") (pintype "bidirectional"))
      (node (ref "U4") (pin "7") (pinfunction "PB8/EIC/AIN2/SCOM4PAD0/TC4_7") (pintype "bidirectional"))
    )
    (net (code "7") (name "A2_PB09_AIN3") (class "Default")
      (node (ref "A2") (pin "1") (pinfunction "1_1") (pintype "bidirectional"))
      (node (ref "U4") (pin "8") (pinfunction "PB9/EIC/AIN3/SCOM4PAD1//TC4_8") (pintype "bidirectional"))
    )
    (net (code "8") (name "A3_PA04_AIN4") (class "Default")
      (node (ref "A2") (pin "2") (pinfunction "2_2") (pintype "bidirectional"))
      (node (ref "U4") (pin "9") (pinfunction "PA4/EIC/REF/AIN4/SCOM0PAD0/TC0_9") (pintype "bidirectional"))
    )
    (net (code "9") (name "A4_PA05_AIN5") (class "Default")
      (node (ref "C78") (pin "1") (pinfunction "1_1") (pintype "passive"))
      (node (ref "R46") (pin "1") (pinfunction "1_1") (pintype "passive"))
      (node (ref "R47") (pin "2") (pinfunction "2_2") (pintype "passive"))
      (node (ref "U4") (pin "10") (pinfunction "PA5/EIC/AIN5/SCOM0PAD1/TC0_10") (pintype "bidirectional"))
    )
    (net (code "10") (name "A5_PB02_AIN10") (class "Default")
      (node (ref "U4") (pin "47") (pinfunction "PB2/EIC/AIN10/SCOM5PAD0_47") (pintype "bidirectional"))
    )
    (net (code "11") (name "AO_PA02_AINO{slash}DAC") (class "Default")
      (node (ref "A0") (pin "1") (pinfunction "1_1") (pintype "bidirectional"))
      (node (ref "U4") (pin "3") (pinfunction "PA2/EIC/AIN0_3") (pintype "bidirectional"))
    )
    (net (code "12") (name "BT_ANT") (class "Default")
      (node (ref "C9") (pin "2") (pinfunction "2_2") (pintype "passive"))
      (node (ref "R22") (pin "1") (pinfunction "1_1") (pintype "passive"))
      (node (ref "U1") (pin "32") (pinfunction "BT_ANT_32") (pintype "bidirectional"))
    )
    (net (code "13") (name "CLK") (class "Default")
      (node (ref "J11") (pin "T5") (pinfunction "CLK_T5") (pintype "bidirectional"))
      (node (ref "R64") (pin "1") (pinfunction "1_1") (pintype "passive"))
      (node (ref "R65") (pin "1") (pinfunction "1_1") (pintype "passive"))
    )
    (net (code "14") (name "CMD{slash}DI") (class "Default")
      (node (ref "J11") (pin "T3") (pinfunction "CMD_T3") (pintype "bidirectional"))
      (node (ref "R62") (pin "1") (pinfunction "1_1") (pintype "passive"))
      (node (ref "R63") (pin "1") (pinfunction "1_1") (pintype "passive"))
    )
    (net (code "15") (name "D0{slash}RX_PA11_TCC0-W3") (class "Default")
      (node (ref "R8") (pin "2") (pinfunction "2_2") (pintype "passive"))
      (node (ref "U4") (pin "16") (pinfunction "PA11/EIC/AIN19/SCOM2PAD3+/TC1_16") (pintype "bidirectional"))
    )
    (net (code "16") (name "D1{slash}TX_PA10_TCC0-W2") (class "Default")
      (node (ref "R51") (pin "1") (pinfunction "1_1") (pintype "passive"))
      (node (ref "U4") (pin "15") (pinfunction "PA10/EIC/AIN18/SCOM2PAD2+/TC1_15") (pintype "bidirectional"))
    )
    (net (code "17") (name "D2_PA08_TCC0-W0") (class "Default")
      (node (ref "D2") (pin "1") (pinfunction "1_1") (pintype "bidirectional"))
      (node (ref "U4") (pin "13") (pinfunction "PA8/I2C/AIN16/SCOM2PAD0+/TC0_13") (pintype "bidirectional"))
    )
    (net (code "18") (name "D3_PA09_TCC0-W1") (class "Default")
      (node (ref "D2") (pin "2") (pinfunction "2_2") (pintype "bidirectional"))
      (node (ref "U4") (pin "14") (pinfunction "PA9/I2C/EIC/AIN17/SCOM2PAD1+/TC0_14") (pintype "bidirectional"))
    )
    (net (code "19") (name "D4_PA14_TCC0-W4") (class "Default")
      (node (ref "D4") (pin "1") (pinfunction "1_1") (pintype "bidirectional"))
      (node (ref "U4") (pin "23") (pinfunction "PA14/XIN/EIC/SCOM2PAD2+/TC3_23") (pintype "bidirectional"))
    )
    (net (code "20") (name "D5_PA15_TCC0-W5") (class "Default")
      (node (ref "D4") (pin "2") (pinfunction "2_2") (pintype "bidirectional"))
      (node (ref "U4") (pin "24") (pinfunction "PA15/XOUT/EIC/SCOM2PAD3+/TC3_24") (pintype "bidirectional"))
    )
    (net (code "21") (name "D7_DGI_GPIO1") (class "Default")
      (node (ref "R24") (pin "2") (pinfunction "2_2") (pintype "passive"))
      (node (ref "U4") (pin "30") (pinfunction "PA21/EIC/SCOM5PAD3+_30") (pintype "bidirectional"))
    )
    (net (code "22") (name "D8_DGI_GPIO2") (class "Default")
      (node (ref "J11") (pin "T2") (pinfunction "CD/DAT3_T2") (pintype "bidirectional"))
      (node (ref "R10") (pin "1") (pinfunction "1_1") (pintype "passive"))
      (node (ref "R33") (pin "1") (pinfunction "1_1") (pintype "passive"))
      (node (ref "U4") (pin "11") (pinfunction "PA6/EIC/AIN6/SCOM0PAD2/TC1_11") (pintype "bidirectional"))
    )
    (net (code "23") (name "D9_DGI_GPIO3") (class "Default")
      (node (ref "R2") (pin "2") (pinfunction "2_2") (pintype "passive"))
      (node (ref "U4") (pin "12") (pinfunction "PA7/EIC/AIN7/SCOM0PAD3/TC1_12") (pintype "bidirectional"))
    )
    (net (code "24") (name "D10_SS") (class "Default")
      (node (ref "R25") (pin "2") (pinfunction "2_2") (pintype "passive"))
      (node (ref "U4") (pin "27") (pinfunction "PA18/EIC/SCOM1PAD2+/TC3_27") (pintype "bidirectional"))
    )
    (net (code "25") (name "D11_MOSI") (class "Default")
      (node (ref "R34") (pin "2") (pinfunction "2_2") (pintype "passive"))
      (node (ref "R38") (pin "1") (pinfunction "1_1") (pintype "passive"))
      (node (ref "U4") (pin "25") (pinfunction "PA16/I2C/EIC/SCOM1PAD0+/TC2_25") (pintype "bidirectional"))
    )
    (net (code "26") (name "D12_MISO") (class "Default")
      (node (ref "R42") (pin "2") (pinfunction "2_2") (pintype "passive"))
      (node (ref "U4") (pin "28") (pinfunction "PA19/EIC/SCOM1PAD3+/TC3_28") (pintype "bidirectional"))
    )
    (net (code "27") (name "D13_SCK") (class "Default")
      (node (ref "Q2") (pin "1") (pinfunction "G_1") (pintype "passive"))
      (node (ref "R55") (pin "2") (pinfunction "2_2") (pintype "passive"))
      (node (ref "U4") (pin "26") (pinfunction "PA17/I2C/EIC/SCOM1PAD1+/TC2_26") (pintype "bidirectional"))
    )
    (net (code "28") (name "DAT0{slash}DO") (class "Default")
      (node (ref "J11") (pin "T7") (pinfunction "DAT0_T7") (pintype "bidirectional"))
      (node (ref "R66") (pin "1") (pinfunction "1_1") (pintype "passive"))
      (node (ref "R67") (pin "1") (pinfunction "1_1") (pintype "passive"))
    )
    (net (code "29") (name "DBG_RXD") (class "Default")
      (node (ref "TP7") (pin "T") (pinfunction "T_T") (pintype "bidirectional"))
      (node (ref "U1") (pin "30") (pinfunction "DBG_RXD_30") (pintype "bidirectional"))
    )
    (net (code "30") (name "DBG_TXD") (class "Default")
      (node (ref "TP8") (pin "T") (pinfunction "T_T") (pintype "bidirectional"))
      (node (ref "U1") (pin "29") (pinfunction "DBG_TXD_29") (pintype "bidirectional"))
    )
    (net (code "31") (name "DTR") (class "Default")
      (node (ref "R2") (pin "1") (pinfunction "1_1") (pintype "passive"))
      (node (ref "U1") (pin "37") (pinfunction "DTR_37") (pintype "bidirectional"))
    )
    (net (code "32") (name "GND") (class "Default")
      (node (ref "A0") (pin "4") (pinfunction "4_4") (pintype "bidirectional"))
      (node (ref "A0") (pin "SS1") (pinfunction "SS1_SS1") (pintype "bidirectional"))
      (node (ref "A0") (pin "SS2") (pinfunction "SS2_SS2") (pintype "bidirectional"))
      (node (ref "A2") (pin "4") (pinfunction "4_4") (pintype "bidirectional"))
      (node (ref "A2") (pin "SS1") (pinfunction "SS1_SS1") (pintype "bidirectional"))
      (node (ref "A2") (pin "SS2") (pinfunction "SS2_SS2") (pintype "bidirectional"))
      (node (ref "ANT1") (pin "GND1") (pinfunction "GND1_GND1") (pintype "bidirectional"))
      (node (ref "ANT1") (pin "GND2") (pinfunction "GND2_GND2") (pintype "bidirectional"))
      (node (ref "ANT2") (pin "GND1") (pinfunction "GND1_GND1") (pintype "bidirectional"))
      (node (ref "ANT2") (pin "GND2") (pinfunction "GND2_GND2") (pintype "bidirectional"))
      (node (ref "ANT4") (pin "GND1") (pinfunction "GND1_GND1") (pintype "bidirectional"))
      (node (ref "ANT4") (pin "GND2") (pinfunction "GND2_GND2") (pintype "bidirectional"))
      (node (ref "C1") (pin "2") (pinfunction "2_2") (pintype "passive"))
      (node (ref "C10") (pin "1") (pinfunction "1_1") (pintype "passive"))
      (node (ref "C12") (pin "2") (pinfunction "2_2") (pintype "passive"))
      (node (ref "C13") (pin "1") (pinfunction "1_1") (pintype "passive"))
      (node (ref "C14") (pin "2") (pinfunction "2_2") (pintype "passive"))
      (node (ref "C15") (pin "1") (pinfunction "1_1") (pintype "passive"))
      (node (ref "C16") (pin "1") (pinfunction "1_1") (pintype "passive"))
      (node (ref "C17") (pin "2") (pinfunction "2_2") (pintype "passive"))
      (node (ref "C18") (pin "1") (pinfunction "1_1") (pintype "passive"))
      (node (ref "C19") (pin "1") (pinfunction "1_1") (pintype "passive"))
      (node (ref "C2") (pin "2") (pinfunction "2_2") (pintype "passive"))
      (node (ref "C20") (pin "2") (pinfunction "2_2") (pintype "passive"))
      (node (ref "C21") (pin "1") (pinfunction "1_1") (pintype "passive"))
      (node (ref "C22") (pin "2") (pinfunction "2_2") (pintype "passive"))
      (node (ref "C23") (pin "2") (pinfunction "2_2") (pintype "passive"))
      (node (ref "C24") (pin "2") (pinfunction "2_2") (pintype "passive"))
      (node (ref "C25") (pin "2") (pinfunction "2_2") (pintype "passive"))
      (node (ref "C26") (pin "2") (pinfunction "2_2") (pintype "passive"))
      (node (ref "C27") (pin "1") (pinfunction "1_1") (pintype "passive"))
      (node (ref "C28") (pin "1") (pinfunction "1_1") (pintype "passive"))
      (node (ref "C29") (pin "2") (pinfunction "2_2") (pintype "passive"))
      (node (ref "C3") (pin "-") (pinfunction "-_-") (pintype "passive"))
      (node (ref "C30") (pin "1") (pinfunction "1_1") (pintype "passive"))
      (node (ref "C31") (pin "1") (pinfunction "1_1") (pintype "passive"))
      (node (ref "C32") (pin "1") (pinfunction "1_1") (pintype "passive"))
      (node (ref "C33") (pin "1") (pinfunction "1_1") (pintype "passive"))
      (node (ref "C34") (pin "1") (pinfunction "1_1") (pintype "passive"))
      (node (ref "C35") (pin "1") (pinfunction "1_1") (pintype "passive"))
      (node (ref "C36") (pin "1") (pinfunction "1_1") (pintype "passive"))
      (node (ref "C38") (pin "1") (pinfunction "1_1") (pintype "passive"))
      (node (ref "C39") (pin "1") (pinfunction "1_1") (pintype "passive"))
      (node (ref "C4") (pin "2") (pinfunction "2_2") (pintype "passive"))
      (node (ref "C40") (pin "-") (pinfunction "-_-") (pintype "passive"))
      (node (ref "C45") (pin "1") (pinfunction "1_1") (pintype "passive"))
      (node (ref "C46") (pin "1") (pinfunction "1_1") (pintype "passive"))
      (node (ref "C49") (pin "1") (pinfunction "1_1") (pintype "passive"))
      (node (ref "C5") (pin "1") (pinfunction "1_1") (pintype "passive"))
      (node (ref "C50") (pin "1") (pinfunction "1_1") (pintype "passive"))
      (node (ref "C51") (pin "1") (pinfunction "1_1") (pintype "passive"))
      (node (ref "C52") (pin "1") (pinfunction "1_1") (pintype "passive"))
      (node (ref "C56") (pin "1") (pinfunction "1_1") (pintype "passive"))
      (node (ref "C57") (pin "1") (pinfunction "1_1") (pintype "passive"))
      (node (ref "C58") (pin "1") (pinfunction "1_1") (pintype "passive"))
      (node (ref "C59") (pin "2") (pinfunction "2_2") (pintype "passive"))
      (node (ref "C6") (pin "1") (pinfunction "1_1") (pintype "passive"))
      (node (ref "C60") (pin "1") (pinfunction "1_1") (pintype "passive"))
      (node (ref "C61") (pin "1") (pinfunction "1_1") (pintype "passive"))
      (node (ref "C62") (pin "1") (pinfunction "1_1") (pintype "passive"))
      (node (ref "C66") (pin "1") (pinfunction "1_1") (pintype "passive"))
      (node (ref "C67") (pin "1") (pinfunction "1_1") (pintype "passive"))
      (node (ref "C68") (pin "1") (pinfunction "1_1") (pintype "passive"))
      (node (ref "C69") (pin "1") (pinfunction "1_1") (pintype "passive"))
      (node (ref "C7") (pin "2") (pinfunction "2_2") (pintype "passive"))
      (node (ref "C70") (pin "1") (pinfunction "1_1") (pintype "passive"))
      (node (ref "C71") (pin "1") (pinfunction "1_1") (pintype "passive"))
      (node (ref "C73") (pin "2") (pinfunction "2_2") (pintype "passive"))
      (node (ref "C74") (pin "1") (pinfunction "1_1") (pintype "passive"))
      (node (ref "C75") (pin "1") (pinfunction "1_1") (pintype "passive"))
      (node (ref "C76") (pin "1") (pinfunction "1_1") (pintype "passive"))
      (node (ref "C77") (pin "1") (pinfunction "1_1") (pintype "passive"))
      (node (ref "C78") (pin "2") (pinfunction "2_2") (pintype "passive"))
      (node (ref "C8") (pin "1") (pinfunction "1_1") (pintype "passive"))
      (node (ref "C80") (pin "1") (pinfunction "1_1") (pintype "passive"))
      (node (ref "C81") (pin "1") (pinfunction "1_1") (pintype "passive"))
      (node (ref "C82") (pin "1") (pinfunction "1_1") (pintype "passive"))
      (node (ref "C83") (pin "1") (pinfunction "1_1") (pintype "passive"))
      (node (ref "C84") (pin "1") (pinfunction "1_1") (pintype "passive"))
      (node (ref "C85") (pin "2") (pinfunction "2_2") (pintype "passive"))
      (node (ref "C86") (pin "1") (pinfunction "1_1") (pintype "passive"))
      (node (ref "C9") (pin "1") (pinfunction "1_1") (pintype "passive"))
      (node (ref "D1") (pin "2") (pinfunction "1_2") (pintype "bidirectional"))
      (node (ref "D10") (pin "2") (pinfunction "1_2") (pintype "bidirectional"))
      (node (ref "D11") (pin "2") (pinfunction "1_2") (pintype "bidirectional"))
      (node (ref "D12") (pin "2") (pinfunction "1_2") (pintype "bidirectional"))
      (node (ref "D13") (pin "2") (pinfunction "1_2") (pintype "bidirectional"))
      (node (ref "D2") (pin "4") (pinfunction "4_4") (pintype "bidirectional"))
      (node (ref "D2") (pin "SS1") (pinfunction "SS1_SS1") (pintype "bidirectional"))
      (node (ref "D2") (pin "SS2") (pinfunction "SS2_SS2") (pintype "bidirectional"))
      (node (ref "D21") (pin "2") (pinfunction "1_2") (pintype "bidirectional"))
      (node (ref "D4") (pin "4") (pinfunction "4_4") (pintype "bidirectional"))
      (node (ref "D4") (pin "SS1") (pinfunction "SS1_SS1") (pintype "bidirectional"))
      (node (ref "D4") (pin "SS2") (pinfunction "SS2_SS2") (pintype "bidirectional"))
      (node (ref "D6") (pin "2") (pinfunction "1_2") (pintype "bidirectional"))
      (node (ref "D7") (pin "2") (pinfunction "1_2") (pintype "bidirectional"))
      (node (ref "D8") (pin "2") (pinfunction "1_2") (pintype "bidirectional"))
      (node (ref "D9") (pin "2") (pinfunction "1_2") (pintype "bidirectional"))
      (node (ref "I2C") (pin "4") (pinfunction "4_4") (pintype "bidirectional"))
      (node (ref "I2C") (pin "SS1") (pinfunction "SS1_SS1") (pintype "bidirectional"))
      (node (ref "I2C") (pin "SS2") (pinfunction "SS2_SS2") (pintype "bidirectional"))
      (node (ref "J10") (pin "2") (pinfunction "2_2") (pintype "bidirectional"))
      (node (ref "J11") (pin "PAD") (pinfunction "PAD_PAD") (pintype "bidirectional"))
      (node (ref "J11") (pin "PAD1") (pinfunction "PAD_PAD1") (pintype "bidirectional"))
      (node (ref "J11") (pin "PAD2") (pinfunction "PAD_PAD2") (pintype "bidirectional"))
      (node (ref "J11") (pin "PAD3") (pinfunction "PAD_PAD3") (pintype "bidirectional"))
      (node (ref "J11") (pin "T6") (pinfunction "VSS_T6") (pintype "bidirectional"))
      (node (ref "J2") (pin "-") (pinfunction "2_-") (pintype "bidirectional"))
      (node (ref "J2") (pin "3") (pinfunction "3_3") (pintype "bidirectional"))
      (node (ref "J2") (pin "4") (pinfunction "4_4") (pintype "bidirectional"))
      (node (ref "J9") (pin "5") (pinfunction "GND_5") (pintype "bidirectional"))
      (node (ref "J9") (pin "P1") (pinfunction "GND_P1") (pintype "bidirectional"))
      (node (ref "J9") (pin "P3") (pinfunction "GND_P3") (pintype "bidirectional"))
      (node (ref "J9") (pin "P4") (pinfunction "GND_P4") (pintype "bidirectional"))
      (node (ref "J9") (pin "P5") (pinfunction "GND_P5") (pintype "bidirectional"))
      (node (ref "J9") (pin "P6") (pinfunction "GND_P6") (pintype "bidirectional"))
      (node (ref "K2") (pin "2") (pinfunction "A1_2") (pintype "bidirectional"))
      (node (ref "LED1") (pin "2") (pinfunction "VSS_2") (pintype "bidirectional"))
      (node (ref "Q1") (pin "2") (pinfunction "S_2") (pintype "passive"))
      (node (ref "Q2") (pin "2") (pinfunction "S_2") (pintype "passive"))
      (node (ref "Q3") (pin "2") (pinfunction "S_2") (pintype "passive"))
      (node (ref "Q7") (pin "2") (pinfunction "S_2") (pintype "passive"))
      (node (ref "R1") (pin "1") (pinfunction "1_1") (pintype "passive"))
      (node (ref "R10") (pin "2") (pinfunction "2_2") (pintype "passive"))
      (node (ref "R15") (pin "2") (pinfunction "2_2") (pintype "passive"))
      (node (ref "R18") (pin "2") (pinfunction "2_2") (pintype "passive"))
      (node (ref "R19") (pin "2") (pinfunction "2_2") (pintype "passive"))
      (node (ref "R20") (pin "2") (pinfunction "2_2") (pintype "passive"))
      (node (ref "R39") (pin "1") (pinfunction "1_1") (pintype "passive"))
      (node (ref "R41") (pin "1") (pinfunction "1_1") (pintype "passive"))
      (node (ref "R47") (pin "1") (pinfunction "1_1") (pintype "passive"))
      (node (ref "R50") (pin "1") (pinfunction "1_1") (pintype "passive"))
      (node (ref "R52") (pin "1") (pinfunction "1_1") (pintype "passive"))
      (node (ref "R54") (pin "1") (pinfunction "1_1") (pintype "passive"))
      (node (ref "R55") (pin "1") (pinfunction "1_1") (pintype "passive"))
      (node (ref "R59") (pin "1") (pinfunction "1_1") (pintype "passive"))
      (node (ref "R60") (pin "1") (pinfunction "1_1") (pintype "passive"))
      (node (ref "TP2") (pin "T") (pinfunction "T_T") (pintype "bidirectional"))
      (node (ref "U1") (pin "14") (pinfunction "GND_14") (pintype "bidirectional"))
      (node (ref "U1") (pin "27") (pinfunction "GND_27") (pintype "bidirectional"))
      (node (ref "U1") (pin "31") (pinfunction "GND_31") (pintype "bidirectional"))
      (node (ref "U1") (pin "40") (pinfunction "GND_40") (pintype "bidirectional"))
      (node (ref "U1") (pin "42") (pinfunction "GND_42") (pintype "bidirectional"))
      (node (ref "U1") (pin "44") (pinfunction "GND_44") (pintype "bidirectional"))
      (node (ref "U1") (pin "45") (pinfunction "GND_45") (pintype "bidirectional"))
      (node (ref "U1") (pin "48") (pinfunction "GND_48") (pintype "bidirectional"))
      (node (ref "U1") (pin "49") (pinfunction "GND_49") (pintype "bidirectional"))
      (node (ref "U3") (pin "1") (pinfunction "PGND_1") (pintype "bidirectional"))
      (node (ref "U3") (pin "3") (pinfunction "AGND_3") (pintype "bidirectional"))
      (node (ref "U3") (pin "6") (pinfunction "MODE_6") (pintype "bidirectional"))
      (node (ref "U3") (pin "9") (pinfunction "PAD_9") (pintype "bidirectional"))
      (node (ref "U4") (pin "18") (pinfunction "GND1_18") (pintype "power_in"))
      (node (ref "U4") (pin "35") (pinfunction "GND2_35") (pintype "power_in"))
      (node (ref "U4") (pin "42") (pinfunction "GND3_42") (pintype "power_in"))
      (node (ref "U4") (pin "5") (pinfunction "GNDANA_5") (pintype "power_in"))
      (node (ref "U4") (pin "PAD") (pinfunction "GND1_PAD") (pintype "power_in"))
      (node (ref "U5") (pin "10") (pinfunction "GND_10") (pintype "bidirectional"))
      (node (ref "U5") (pin "13") (pinfunction "USB_DET_13") (pintype "bidirectional"))
      (node (ref "U5") (pin "6") (pinfunction "ENB_6") (pintype "bidirectional"))
      (node (ref "U5") (pin "8") (pinfunction "GND_8") (pintype "bidirectional"))
      (node (ref "U5") (pin "PAD") (pinfunction "PAD_PAD") (pintype "bidirectional"))
      (node (ref "URAT") (pin "4") (pinfunction "4_4") (pintype "bidirectional"))
      (node (ref "URAT") (pin "SS1") (pinfunction "SS1_SS1") (pintype "bidirectional"))
      (node (ref "URAT") (pin "SS2") (pinfunction "SS2_SS2") (pintype "bidirectional"))
    )
    (net (code "33") (name "GNSS_ANT") (class "Default")
      (node (ref "C33") (pin "2") (pinfunction "2_2") (pintype "passive"))
      (node (ref "R28") (pin "2") (pinfunction "2_2") (pintype "passive"))
      (node (ref "U1") (pin "15") (pinfunction "GNSS_ANT_15") (pintype "bidirectional"))
    )
    (net (code "34") (name "GNSS_RXD") (class "Default")
      (node (ref "R49") (pin "2") (pinfunction "2_2") (pintype "passive"))
      (node (ref "R53") (pin "2") (pinfunction "2_2") (pintype "passive"))
      (node (ref "R54") (pin "2") (pinfunction "2_2") (pintype "passive"))
      (node (ref "TP10") (pin "T") (pinfunction "T_T") (pintype "bidirectional"))
      (node (ref "U1") (pin "23") (pinfunction "GNSS_RXD_23") (pintype "bidirectional"))
    )
    (net (code "35") (name "GNSS_TXD") (class "Default")
      (node (ref "R27") (pin "1") (pinfunction "1_1") (pintype "passive"))
      (node (ref "R48") (pin "2") (pinfunction "2_2") (pintype "passive"))
      (node (ref "TP9") (pin "T") (pinfunction "T_T") (pintype "bidirectional"))
      (node (ref "U1") (pin "22") (pinfunction "GNSS_TXD_22") (pintype "bidirectional"))
    )
    (net (code "36") (name "GNSS_VCC_EN") (class "Default")
      (node (ref "U1") (pin "28") (pinfunction "GNSS_VCC_EN_28") (pintype "bidirectional"))
    )
    (net (code "37") (name "LOUDSPKN") (class "Default")
      (node (ref "C49") (pin "2") (pinfunction "2_2") (pintype "passive"))
      (node (ref "C57") (pin "2") (pinfunction "2_2") (pintype "passive"))
      (node (ref "R30") (pin "1") (pinfunction "1_1") (pintype "passive"))
      (node (ref "U1") (pin "53") (pinfunction "LOUDSPKN_53") (pintype "bidirectional"))
    )
    (net (code "38") (name "LOUDSPKP") (class "Default")
      (node (ref "C50") (pin "2") (pinfunction "2_2") (pintype "passive"))
      (node (ref "C56") (pin "2") (pinfunction "2_2") (pintype "passive"))
      (node (ref "R31") (pin "1") (pinfunction "1_1") (pintype "passive"))
      (node (ref "U1") (pin "54") (pinfunction "LOUDSPKP_54") (pintype "bidirectional"))
    )
    (net (code "39") (name "MICN") (class "Default")
      (node (ref "U1") (pin "2") (pinfunction "MICN_2") (pintype "bidirectional"))
    )
    (net (code "40") (name "MICP") (class "Default")
      (node (ref "R68") (pin "1") (pinfunction "1_1") (pintype "passive"))
      (node (ref "U1") (pin "1") (pinfunction "MICP_1") (pintype "bidirectional"))
    )
    (net (code "41") (name "NETLIGHT") (class "Default")
      (node (ref "Q1") (pin "1") (pinfunction "G_1") (pintype "passive"))
      (node (ref "R50") (pin "2") (pinfunction "2_2") (pintype "passive"))
      (node (ref "U1") (pin "47") (pinfunction "NETLIGHT_47") (pintype "bidirectional"))
    )
    (net (code "42") (name "Net-(ANT1-PadD)") (class "Default")
      (node (ref "ANT1") (pin "D") (pinfunction "D_D") (pintype "bidirectional"))
      (node (ref "C36") (pin "2") (pinfunction "2_2") (pintype "passive"))
      (node (ref "R29") (pin "2") (pinfunction "2_2") (pintype "passive"))
    )
    (net (code "43") (name "Net-(ANT2-PadD)") (class "Default")
      (node (ref "ANT2") (pin "D") (pinfunction "D_D") (pintype "bidirectional"))
      (node (ref "C34") (pin "2") (pinfunction "2_2") (pintype "passive"))
      (node (ref "R22") (pin "2") (pinfunction "2_2") (pintype "passive"))
    )
    (net (code "44") (name "Net-(ANT4-PadD)") (class "Default")
      (node (ref "ANT4") (pin "D") (pinfunction "D_D") (pintype "bidirectional"))
      (node (ref "C27") (pin "2") (pinfunction "2_2") (pintype "passive"))
      (node (ref "L1") (pin "2") (pinfunction "2_2") (pintype "passive"))
      (node (ref "R28") (pin "1") (pinfunction "1_1") (pintype "passive"))
    )
    (net (code "45") (name "Net-(C37-Pad1)") (class "Default")
      (node (ref "C37") (pin "1") (pinfunction "1_1") (pintype "passive"))
      (node (ref "C59") (pin "1") (pinfunction "1_1") (pintype "passive"))
      (node (ref "C60") (pin "2") (pinfunction "2_2") (pintype "passive"))
      (node (ref "C64") (pin "2") (pinfunction "2_2") (pintype "passive"))
      (node (ref "C73") (pin "1") (pinfunction "1_1") (pintype "passive"))
      (node (ref "L11") (pin "1") (pinfunction "1_1") (pintype "passive"))
      (node (ref "R7") (pin "2") (pinfunction "2_2") (pintype "passive"))
    )
    (net (code "46") (name "Net-(C37-Pad2)") (class "Default")
      (node (ref "C37") (pin "2") (pinfunction "2_2") (pintype "passive"))
      (node (ref "C58") (pin "2") (pinfunction "2_2") (pintype "passive"))
      (node (ref "C61") (pin "2") (pinfunction "2_2") (pintype "passive"))
      (node (ref "C65") (pin "2") (pinfunction "2_2") (pintype "passive"))
      (node (ref "C74") (pin "2") (pinfunction "2_2") (pintype "passive"))
      (node (ref "L12") (pin "1") (pinfunction "1_1") (pintype "passive"))
      (node (ref "R69") (pin "2") (pinfunction "2_2") (pintype "passive"))
    )
    (net (code "47") (name "Net-(C48-Pad1)") (class "Default")
      (node (ref "C48") (pin "1") (pinfunction "1_1") (pintype "passive"))
      (node (ref "C51") (pin "2") (pinfunction "2_2") (pintype "passive"))
      (node (ref "C53") (pin "1") (pinfunction "1_1") (pintype "passive"))
      (node (ref "R30") (pin "2") (pinfunction "2_2") (pintype "passive"))
      (node (ref "R70") (pin "1") (pinfunction "1_1") (pintype "passive"))
    )
    (net (code "48") (name "Net-(C48-Pad2)") (class "Default")
      (node (ref "C48") (pin "2") (pinfunction "2_2") (pintype "passive"))
      (node (ref "C52") (pin "2") (pinfunction "2_2") (pintype "passive"))
      (node (ref "C54") (pin "1") (pinfunction "1_1") (pintype "passive"))
      (node (ref "R31") (pin "2") (pinfunction "2_2") (pintype "passive"))
      (node (ref "R71") (pin "1") (pinfunction "1_1") (pintype "passive"))
    )
    (net (code "49") (name "Net-(C62-Pad2)") (class "Default")
      (node (ref "C62") (pin "2") (pinfunction "2_2") (pintype "passive"))
      (node (ref "C67") (pin "2") (pinfunction "2_2") (pintype "passive"))
      (node (ref "R35") (pin "1") (pinfunction "1_1") (pintype "passive"))
      (node (ref "R68") (pin "2") (pinfunction "2_2") (pintype "passive"))
    )
    (net (code "50") (name "Net-(C64-Pad1)") (class "Default")
      (node (ref "C64") (pin "1") (pinfunction "1_1") (pintype "passive"))
      (node (ref "R36") (pin "2") (pinfunction "2_2") (pintype "passive"))
      (node (ref "R7") (pin "1") (pinfunction "1_1") (pintype "passive"))
    )
    (net (code "51") (name "Net-(C65-Pad1)") (class "Default")
      (node (ref "C65") (pin "1") (pinfunction "1_1") (pintype "passive"))
      (node (ref "R37") (pin "2") (pinfunction "2_2") (pintype "passive"))
      (node (ref "R69") (pin "1") (pinfunction "1_1") (pintype "passive"))
    )
    (net (code "52") (name "Net-(C66-Pad2)") (class "Default")
      (node (ref "C66") (pin "2") (pinfunction "2_2") (pintype "passive"))
      (node (ref "C69") (pin "2") (pinfunction "2_2") (pintype "passive"))
      (node (ref "L5") (pin "1") (pinfunction "1_1") (pintype "passive"))
      (node (ref "R35") (pin "2") (pinfunction "2_2") (pintype "passive"))
    )
    (net (code "53") (name "Net-(D3-Pad-)") (class "Default")
      (node (ref "D3") (pin "-") (pinfunction "-_-") (pintype "passive"))
      (node (ref "R43") (pin "2") (pinfunction "2_2") (pintype "passive"))
    )
    (net (code "54") (name "Net-(D5-Pad-)") (class "Default")
      (node (ref "D5") (pin "-") (pinfunction "-_-") (pintype "passive"))
      (node (ref "R23") (pin "2") (pinfunction "2_2") (pintype "passive"))
    )
    (net (code "55") (name "Net-(D6-2)") (class "Default")
      (node (ref "D6") (pin "1") (pinfunction "2_1") (pintype "bidirectional"))
      (node (ref "L5") (pin "2") (pinfunction "2_2") (pintype "passive"))
      (node (ref "R32") (pin "2") (pinfunction "2_2") (pintype "passive"))
    )
    (net (code "56") (name "Net-(D7-2)") (class "Default")
      (node (ref "C54") (pin "2") (pinfunction "2_2") (pintype "passive"))
      (node (ref "D7") (pin "1") (pinfunction "2_1") (pintype "bidirectional"))
      (node (ref "R71") (pin "2") (pinfunction "2_2") (pintype "passive"))
      (node (ref "SPK") (pin "1") (pinfunction "+_1") (pintype "bidirectional"))
    )
    (net (code "57") (name "Net-(D8-2)") (class "Default")
      (node (ref "D8") (pin "1") (pinfunction "2_1") (pintype "bidirectional"))
      (node (ref "J9") (pin "2") (pinfunction "DM_2") (pintype "bidirectional"))
      (node (ref "R21") (pin "1") (pinfunction "1_1") (pintype "passive"))
      (node (ref "TP3") (pin "T") (pinfunction "T_T") (pintype "bidirectional"))
    )
    (net (code "58") (name "Net-(D9-2)") (class "Default")
      (node (ref "D9") (pin "1") (pinfunction "2_1") (pintype "bidirectional"))
      (node (ref "J9") (pin "3") (pinfunction "DP_3") (pintype "bidirectional"))
      (node (ref "R11") (pin "1") (pinfunction "1_1") (pintype "passive"))
      (node (ref "TP4") (pin "T") (pinfunction "T_T") (pintype "bidirectional"))
    )
    (net (code "59") (name "Net-(D10-2)") (class "Default")
      (node (ref "D10") (pin "1") (pinfunction "2_1") (pintype "bidirectional"))
      (node (ref "J1") (pin "6") (pinfunction "6_6") (pintype "bidirectional"))
      (node (ref "R38") (pin "2") (pinfunction "2_2") (pintype "passive"))
    )
    (net (code "60") (name "Net-(D11-2)") (class "Default")
      (node (ref "D11") (pin "1") (pinfunction "2_1") (pintype "bidirectional"))
      (node (ref "J1") (pin "4") (pinfunction "4_4") (pintype "bidirectional"))
      (node (ref "L11") (pin "2") (pinfunction "2_2") (pintype "passive"))
      (node (ref "R4") (pin "2") (pinfunction "2_2") (pintype "passive"))
    )
    (net (code "61") (name "Net-(D12-2)") (class "Default")
      (node (ref "D12") (pin "1") (pinfunction "2_1") (pintype "bidirectional"))
      (node (ref "J1") (pin "3") (pinfunction "3_3") (pintype "bidirectional"))
      (node (ref "L12") (pin "2") (pinfunction "2_2") (pintype "passive"))
      (node (ref "R4") (pin "1") (pinfunction "1_1") (pintype "passive"))
    )
    (net (code "62") (name "Net-(D16-Pad-)") (class "Default")
      (node (ref "D16") (pin "-") (pinfunction "-_-") (pintype "passive"))
      (node (ref "R17") (pin "1") (pinfunction "1_1") (pintype "passive"))
    )
    (net (code "63") (name "Net-(D17-Pad-)") (class "Default")
      (node (ref "D17") (pin "-") (pinfunction "-_-") (pintype "passive"))
      (node (ref "R44") (pin "2") (pinfunction "2_2") (pintype "passive"))
    )
    (net (code "64") (name "Net-(D21-2)") (class "Default")
      (node (ref "C53") (pin "2") (pinfunction "2_2") (pintype "passive"))
      (node (ref "D21") (pin "1") (pinfunction "2_1") (pintype "bidirectional"))
      (node (ref "R70") (pin "2") (pinfunction "2_2") (pintype "passive"))
      (node (ref "SPK") (pin "2") (pinfunction "-_2") (pintype "bidirectional"))
    )
    (net (code "65") (name "Net-(J1-Pad1)") (class "Default")
      (node (ref "J1") (pin "1") (pinfunction "1_1") (pintype "bidirectional"))
      (node (ref "R32") (pin "1") (pinfunction "1_1") (pintype "passive"))
    )
    (net (code "66") (name "Net-(J1-Pad2)") (class "Default")
      (node (ref "J1") (pin "2") (pinfunction "2_2") (pintype "bidirectional"))
      (node (ref "R39") (pin "2") (pinfunction "2_2") (pintype "passive"))
    )
    (net (code "67") (name "Net-(J2-1)") (class "Default")
      (node (ref "C25") (pin "1") (pinfunction "1_1") (pintype "passive"))
      (node (ref "J2") (pin "+") (pinfunction "1_+") (pintype "bidirectional"))
      (node (ref "R46") (pin "2") (pinfunction "2_2") (pintype "passive"))
      (node (ref "U5") (pin "14") (pinfunction "BATT_14") (pintype "bidirectional"))
      (node (ref "U5") (pin "16") (pinfunction "BATT_16") (pintype "bidirectional"))
    )
    (net (code "68") (name "Net-(J9-VCC)") (class "Default")
      (node (ref "F1") (pin "1") (pinfunction "1_1") (pintype "bidirectional"))
      (node (ref "J9") (pin "1") (pinfunction "VCC_1") (pintype "bidirectional"))
      (node (ref "TP1") (pin "T") (pinfunction "T_T") (pintype "bidirectional"))
    )
    (net (code "69") (name "Net-(J10-Pad3)") (class "Default")
      (node (ref "J10") (pin "3") (pinfunction "3_3") (pintype "bidirectional"))
      (node (ref "R5") (pin "1") (pinfunction "1_1") (pintype "passive"))
    )
    (net (code "70") (name "Net-(J10-Pad4)") (class "Default")
      (node (ref "J10") (pin "4") (pinfunction "4_4") (pintype "bidirectional"))
      (node (ref "R6") (pin "1") (pinfunction "1_1") (pintype "passive"))
    )
    (net (code "71") (name "Net-(J11-CLK1-PadP3)") (class "Default")
      (node (ref "J11") (pin "P3") (pinfunction "CLK1_P3") (pintype "bidirectional"))
      (node (ref "J11") (pin "P3B") (pinfunction "CLK1_P3B") (pintype "bidirectional"))
      (node (ref "R57") (pin "2") (pinfunction "2_2") (pintype "passive"))
    )
    (net (code "72") (name "Net-(J11-I{slash}O-PadP7)") (class "Default")
      (node (ref "J11") (pin "P7") (pinfunction "I/O_P7") (pintype "bidirectional"))
      (node (ref "J11") (pin "P7B") (pinfunction "I/O_P7B") (pintype "bidirectional"))
      (node (ref "R58") (pin "2") (pinfunction "2_2") (pintype "passive"))
    )
    (net (code "73") (name "Net-(J11-RST-PadP2)") (class "Default")
      (node (ref "J11") (pin "P2") (pinfunction "RST_P2") (pintype "bidirectional"))
      (node (ref "J11") (pin "P2B") (pinfunction "RST_P2B") (pintype "bidirectional"))
      (node (ref "R56") (pin "2") (pinfunction "2_2") (pintype "passive"))
    )
    (net (code "74") (name "Net-(J11-VPP-PadP6)") (class "Default")
      (node (ref "J11") (pin "P6") (pinfunction "VPP_P6") (pintype "bidirectional"))
      (node (ref "J11") (pin "P6B") (pinfunction "VPP_P6B") (pintype "bidirectional"))
    )
    (net (code "75") (name "Net-(K1-A1)") (class "Default")
      (node (ref "K1") (pin "2") (pinfunction "A1_2") (pintype "bidirectional"))
      (node (ref "R1") (pin "2") (pinfunction "2_2") (pintype "passive"))
    )
    (net (code "76") (name "Net-(L1-Pad1)") (class "Default")
      (node (ref "L1") (pin "1") (pinfunction "1_1") (pintype "passive"))
      (node (ref "R3") (pin "1") (pinfunction "1_1") (pintype "passive"))
    )
    (net (code "77") (name "Net-(L3-Pad1)") (class "Default")
      (node (ref "L3") (pin "1") (pinfunction "1_1") (pintype "passive"))
      (node (ref "U5") (pin "3") (pinfunction "SW_3") (pintype "bidirectional"))
      (node (ref "U5") (pin "4") (pinfunction "SW_4") (pintype "bidirectional"))
    )
    (net (code "78") (name "Net-(LED1-DIN)") (class "Default")
      (node (ref "LED1") (pin "3") (pinfunction "DIN_3") (pintype "bidirectional"))
      (node (ref "R25") (pin "1") (pinfunction "1_1") (pintype "passive"))
    )
    (net (code "79") (name "Net-(Q1-D)") (class "Default")
      (node (ref "Q1") (pin "3") (pinfunction "D_3") (pintype "passive"))
      (node (ref "R23") (pin "1") (pinfunction "1_1") (pintype "passive"))
    )
    (net (code "80") (name "Net-(Q3-D)") (class "Default")
      (node (ref "Q3") (pin "3") (pinfunction "D_3") (pintype "passive"))
      (node (ref "Q5") (pin "1") (pinfunction "G_1") (pintype "passive"))
      (node (ref "R45") (pin "1") (pinfunction "1_1") (pintype "passive"))
    )
    (net (code "81") (name "Net-(Q3-G)") (class "Default")
      (node (ref "C85") (pin "1") (pinfunction "1_1") (pintype "passive"))
      (node (ref "Q3") (pin "1") (pinfunction "G_1") (pintype "passive"))
      (node (ref "R42") (pin "1") (pinfunction "1_1") (pintype "passive"))
      (node (ref "R60") (pin "2") (pinfunction "2_2") (pintype "passive"))
    )
    (net (code "82") (name "Net-(Q6-G)") (class "Default")
      (node (ref "Q6") (pin "1") (pinfunction "G_1") (pintype "passive"))
      (node (ref "Q7") (pin "3") (pinfunction "D_3") (pintype "passive"))
      (node (ref "R26") (pin "1") (pinfunction "1_1") (pintype "passive"))
    )
    (net (code "83") (name "Net-(Q7-G)") (class "Default")
      (node (ref "C14") (pin "1") (pinfunction "1_1") (pintype "passive"))
      (node (ref "Q7") (pin "1") (pinfunction "G_1") (pintype "passive"))
      (node (ref "R24") (pin "1") (pinfunction "1_1") (pintype "passive"))
      (node (ref "R59") (pin "2") (pinfunction "2_2") (pintype "passive"))
    )
    (net (code "84") (name "Net-(U1-VRTC)") (class "Default")
      (node (ref "R61") (pin "1") (pinfunction "1_1") (pintype "passive"))
      (node (ref "U1") (pin "52") (pinfunction "VRTC_52") (pintype "bidirectional"))
    )
    (net (code "85") (name "Net-(U3-FB)") (class "Default")
      (node (ref "R40") (pin "1") (pinfunction "1_1") (pintype "passive"))
      (node (ref "R41") (pin "2") (pinfunction "2_2") (pintype "passive"))
      (node (ref "U3") (pin "4") (pinfunction "FB_4") (pintype "bidirectional"))
    )
    (net (code "86") (name "Net-(U3-SW)") (class "Default")
      (node (ref "L2") (pin "1") (pinfunction "1_1") (pintype "passive"))
      (node (ref "U3") (pin "2") (pinfunction "SW_2") (pintype "bidirectional"))
    )
    (net (code "87") (name "Net-(U4-PA0{slash}XIN32{slash}EIC{slash}SCOM1PAD0{slash}TC2)") (class "Default")
      (node (ref "C46") (pin "2") (pinfunction "2_2") (pintype "passive"))
      (node (ref "U4") (pin "1") (pinfunction "PA0/XIN32/EIC/SCOM1PAD0/TC2_1") (pintype "bidirectional"))
      (node (ref "X1") (pin "1") (pinfunction "1_1") (pintype "passive"))
    )
    (net (code "88") (name "Net-(U4-PA1{slash}XOUT32{slash}EIC{slash}SCOM1PAD1{slash}TC2)") (class "Default")
      (node (ref "C45") (pin "2") (pinfunction "2_2") (pintype "passive"))
      (node (ref "U4") (pin "2") (pinfunction "PA1/XOUT32/EIC/SCOM1PAD1/TC2_2") (pintype "bidirectional"))
      (node (ref "X1") (pin "2") (pinfunction "2_2") (pintype "passive"))
    )
    (net (code "89") (name "Net-(U4-PA3{slash}EIC{slash}REF{slash}AIN1)") (class "Default")
      (node (ref "C19") (pin "2") (pinfunction "2_2") (pintype "passive"))
      (node (ref "U4") (pin "4") (pinfunction "PA3/EIC/REF/AIN1_4") (pintype "bidirectional"))
    )
    (net (code "90") (name "Net-(U4-RESETN)") (class "Default")
      (node (ref "C1") (pin "1") (pinfunction "1_1") (pintype "passive"))
      (node (ref "D14") (pin "+") (pinfunction "+_+") (pintype "passive"))
      (node (ref "R12") (pin "2") (pinfunction "2_2") (pintype "passive"))
      (node (ref "U4") (pin "40") (pinfunction "RESETN_40") (pintype "bidirectional"))
    )
    (net (code "91") (name "Net-(U5-ISET1)") (class "Default")
      (node (ref "R20") (pin "1") (pinfunction "1_1") (pintype "passive"))
      (node (ref "U5") (pin "11") (pinfunction "ISET1_11") (pintype "bidirectional"))
    )
    (net (code "92") (name "Net-(U5-ISET2)") (class "Default")
      (node (ref "R19") (pin "1") (pinfunction "1_1") (pintype "passive"))
      (node (ref "U5") (pin "12") (pinfunction "ISET2_12") (pintype "bidirectional"))
    )
    (net (code "93") (name "Net-(U5-NTC)") (class "Default")
      (node (ref "R16") (pin "2") (pinfunction "2_2") (pintype "passive"))
      (node (ref "R18") (pin "1") (pinfunction "1_1") (pintype "passive"))
      (node (ref "U5") (pin "7") (pinfunction "NTC_7") (pintype "bidirectional"))
    )
    (net (code "94") (name "Net-(U5-PGND)") (class "Default")
      (node (ref "R15") (pin "1") (pinfunction "1_1") (pintype "passive"))
      (node (ref "U5") (pin "5") (pinfunction "PGND_5") (pintype "bidirectional"))
    )
    (net (code "95") (name "Net-(U5-STAT)") (class "Default")
      (node (ref "R17") (pin "2") (pinfunction "2_2") (pintype "passive"))
      (node (ref "U5") (pin "9") (pinfunction "STAT_9") (pintype "bidirectional"))
    )
    (net (code "96") (name "PA20_D6") (class "Default")
      (node (ref "U4") (pin "29") (pinfunction "PA20/EIC/SCOM5PAD2+_29") (pintype "bidirectional"))
    )
    (net (code "97") (name "PA27_TX_LED") (class "Default")
      (node (ref "R43") (pin "1") (pinfunction "1_1") (pintype "passive"))
      (node (ref "U4") (pin "39") (pinfunction "PA27/EIC_39") (pintype "bidirectional"))
    )
    (net (code "98") (name "PA30_SWCLK{slash}TX") (class "Default")
      (node (ref "R5") (pin "2") (pinfunction "2_2") (pintype "passive"))
      (node (ref "U4") (pin "45") (pinfunction "PA30/EIC/SCOM1PAD2/TC1_45") (pintype "bidirectional"))
      (node (ref "URAT") (pin "2") (pinfunction "2_2") (pintype "bidirectional"))
    )
    (net (code "99") (name "PA31_SWDIO{slash}RX") (class "Default")
      (node (ref "R6") (pin "2") (pinfunction "2_2") (pintype "passive"))
      (node (ref "U4") (pin "46") (pinfunction "PA31/EIC/SCOM1PAD3/TC1_46") (pintype "bidirectional"))
      (node (ref "URAT") (pin "1") (pinfunction "1_1") (pintype "bidirectional"))
    )
    (net (code "100") (name "PB03_RX_LED") (class "Default")
      (node (ref "R44") (pin "1") (pinfunction "1_1") (pintype "passive"))
      (node (ref "U4") (pin "48") (pinfunction "PB3/EIC/AIN11/SCOM5PAD1_48") (pintype "bidirectional"))
    )
    (net (code "101") (name "PB22_TXD") (class "Default")
      (node (ref "R53") (pin "1") (pinfunction "1_1") (pintype "passive"))
      (node (ref "U4") (pin "37") (pinfunction "PB22/EIC/SCOM5PAD2_37") (pintype "bidirectional"))
    )
    (net (code "102") (name "PB23_RXD") (class "Default")
      (node (ref "R27") (pin "2") (pinfunction "2_2") (pintype "passive"))
      (node (ref "U4") (pin "38") (pinfunction "PB23/EIC/SCOM5PAD3_38") (pintype "bidirectional"))
    )
    (net (code "103") (name "PWRKEY") (class "Default")
      (node (ref "K1") (pin "4") (pinfunction "B1_4") (pintype "bidirectional"))
      (node (ref "Q2") (pin "3") (pinfunction "D_3") (pintype "passive"))
      (node (ref "R9") (pin "1") (pinfunction "1_1") (pintype "passive"))
      (node (ref "TP5") (pin "T") (pinfunction "T_T") (pintype "bidirectional"))
      (node (ref "U1") (pin "5") (pinfunction "PWRKEY_5") (pintype "bidirectional"))
    )
    (net (code "104") (name "RF_ANT{slash}GSM") (class "Default")
      (node (ref "C35") (pin "2") (pinfunction "2_2") (pintype "passive"))
      (node (ref "R29") (pin "1") (pinfunction "1_1") (pintype "passive"))
      (node (ref "U1") (pin "41") (pinfunction "RF_ANT_41") (pintype "bidirectional"))
    )
    (net (code "105") (name "RXD") (class "Default")
      (node (ref "R51") (pin "2") (pinfunction "2_2") (pintype "passive"))
      (node (ref "R52") (pin "2") (pinfunction "2_2") (pintype "passive"))
      (node (ref "TP13") (pin "T") (pinfunction "T_T") (pintype "bidirectional"))
      (node (ref "U1") (pin "33") (pinfunction "RXD_33") (pintype "bidirectional"))
    )
    (net (code "106") (name "RXD_AUX") (class "Default")
      (node (ref "R48") (pin "1") (pinfunction "1_1") (pintype "passive"))
      (node (ref "U1") (pin "24") (pinfunction "RXD_AUX_24") (pintype "bidirectional"))
    )
    (net (code "107") (name "SCL") (class "Default")
      (node (ref "I2C") (pin "1") (pinfunction "1_1") (pintype "bidirectional"))
      (node (ref "R13") (pin "1") (pinfunction "1_1") (pintype "passive"))
      (node (ref "U4") (pin "32") (pinfunction "PA23/I2C/EIC/SCOM5PAD1+/TC4_32") (pintype "bidirectional"))
    )
    (net (code "108") (name "SDA") (class "Default")
      (node (ref "I2C") (pin "2") (pinfunction "2_2") (pintype "bidirectional"))
      (node (ref "R14") (pin "1") (pinfunction "1_1") (pintype "passive"))
      (node (ref "U4") (pin "31") (pinfunction "PA22/I2C/EIC/SCOM5PAD0+/TC4_31") (pintype "bidirectional"))
    )
    (net (code "109") (name "SD_CLK") (class "Default")
      (node (ref "R64") (pin "2") (pinfunction "2_2") (pintype "passive"))
      (node (ref "U1") (pin "8") (pinfunction "SD_CLK_8") (pintype "bidirectional"))
    )
    (net (code "110") (name "SD_CMD") (class "Default")
      (node (ref "R62") (pin "2") (pinfunction "2_2") (pintype "passive"))
      (node (ref "U1") (pin "7") (pinfunction "SD_CMD_7") (pintype "bidirectional"))
    )
    (net (code "111") (name "SD_DATA") (class "Default")
      (node (ref "R66") (pin "2") (pinfunction "2_2") (pintype "passive"))
      (node (ref "U1") (pin "9") (pinfunction "SD_DATA_9") (pintype "bidirectional"))
    )
    (net (code "112") (name "SIM1_CLK") (class "Default")
      (node (ref "C5") (pin "2") (pinfunction "2_2") (pintype "passive"))
      (node (ref "R57") (pin "1") (pinfunction "1_1") (pintype "passive"))
      (node (ref "U1") (pin "19") (pinfunction "SIM1_CLK_19") (pintype "bidirectional"))
    )
    (net (code "113") (name "SIM1_DATA") (class "Default")
      (node (ref "C6") (pin "2") (pinfunction "2_2") (pintype "passive"))
      (node (ref "R58") (pin "1") (pinfunction "1_1") (pintype "passive"))
      (node (ref "U1") (pin "21") (pinfunction "SIM1_DATA_21") (pintype "bidirectional"))
    )
    (net (code "114") (name "SIM1_RST") (class "Default")
      (node (ref "C13") (pin "2") (pinfunction "2_2") (pintype "passive"))
      (node (ref "R56") (pin "1") (pinfunction "1_1") (pintype "passive"))
      (node (ref "U1") (pin "20") (pinfunction "SIM1_RST_20") (pintype "bidirectional"))
    )
    (net (code "115") (name "SIM1_VDD") (class "Default")
      (node (ref "C11") (pin "2") (pinfunction "2_2") (pintype "passive"))
      (node (ref "C86") (pin "2") (pinfunction "2_2") (pintype "passive"))
      (node (ref "J11") (pin "P1") (pinfunction "VCC_P1") (pintype "bidirectional"))
      (node (ref "J11") (pin "P1B") (pinfunction "VCC_P1B") (pintype "bidirectional"))
      (node (ref "U1") (pin "18") (pinfunction "SIM1_VDD_18") (pintype "bidirectional"))
    )
    (net (code "116") (name "SIM_GND") (class "Default")
      (node (ref "C11") (pin "1") (pinfunction "1_1") (pintype "passive"))
      (node (ref "J11") (pin "P5") (pinfunction "GND_P5") (pintype "bidirectional"))
      (node (ref "J11") (pin "P5B") (pinfunction "GND_P5B") (pintype "bidirectional"))
      (node (ref "U1") (pin "16") (pinfunction "SIM_GND_16") (pintype "bidirectional"))
    )
    (net (code "117") (name "SPI_MISO") (class "Default")
      (node (ref "R67") (pin "2") (pinfunction "2_2") (pintype "passive"))
      (node (ref "TP16") (pin "T") (pinfunction "T_T") (pintype "bidirectional"))
      (node (ref "U4") (pin "21") (pinfunction "PA12/I2C/EIC/SCOM2PAD0+/TC2_21") (pintype "bidirectional"))
    )
    (net (code "118") (name "SPI_MOSI") (class "Default")
      (node (ref "R63") (pin "2") (pinfunction "2_2") (pintype "passive"))
      (node (ref "TP14") (pin "T") (pinfunction "T_T") (pintype "bidirectional"))
      (node (ref "U4") (pin "19") (pinfunction "PB10/EIC/SCOM4PAD2/TC5_19") (pintype "bidirectional"))
    )
    (net (code "119") (name "SPI_SCK") (class "Default")
      (node (ref "R65") (pin "2") (pinfunction "2_2") (pintype "passive"))
      (node (ref "TP15") (pin "T") (pinfunction "T_T") (pintype "bidirectional"))
      (node (ref "U4") (pin "20") (pinfunction "PB11/EIC/SCOM4PAD3/TC5_20") (pintype "bidirectional"))
    )
    (net (code "120") (name "SPKN") (class "Default")
      (node (ref "R37") (pin "1") (pinfunction "1_1") (pintype "passive"))
      (node (ref "U1") (pin "4") (pinfunction "SPKN_4") (pintype "bidirectional"))
    )
    (net (code "121") (name "SPKP") (class "Default")
      (node (ref "R36") (pin "1") (pinfunction "1_1") (pintype "passive"))
      (node (ref "U1") (pin "3") (pinfunction "SPKP_3") (pintype "bidirectional"))
    )
    (net (code "122") (name "TXD") (class "Default")
      (node (ref "R8") (pin "1") (pinfunction "1_1") (pintype "passive"))
      (node (ref "TP11") (pin "T") (pinfunction "T_T") (pintype "bidirectional"))
      (node (ref "U1") (pin "34") (pinfunction "TXD_34") (pintype "bidirectional"))
    )
    (net (code "123") (name "TXD_AUX") (class "Default")
      (node (ref "R49") (pin "1") (pinfunction "1_1") (pintype "passive"))
      (node (ref "U1") (pin "25") (pinfunction "TXD_AUX_25") (pintype "bidirectional"))
    )
    (net (code "124") (name "USB_D+") (class "Default")
      (node (ref "R11") (pin "2") (pinfunction "2_2") (pintype "passive"))
      (node (ref "U4") (pin "34") (pinfunction "PA25/EIC/SCOM3PAD3+/TC5_34") (pintype "bidirectional"))
    )
    (net (code "125") (name "USB_D-") (class "Default")
      (node (ref "R21") (pin "2") (pinfunction "2_2") (pintype "passive"))
      (node (ref "U4") (pin "33") (pinfunction "PA24/EIC/SCOM3PAD2+/TC5_33") (pintype "bidirectional"))
    )
    (net (code "126") (name "VBAT") (class "Default")
      (node (ref "C3") (pin "+") (pinfunction "+_+") (pintype "passive"))
      (node (ref "C4") (pin "1") (pinfunction "1_1") (pintype "passive"))
      (node (ref "C40") (pin "+") (pinfunction "+_+") (pintype "passive"))
      (node (ref "C80") (pin "2") (pinfunction "2_2") (pintype "passive"))
      (node (ref "C81") (pin "2") (pinfunction "2_2") (pintype "passive"))
      (node (ref "C82") (pin "2") (pinfunction "2_2") (pintype "passive"))
      (node (ref "D13") (pin "1") (pinfunction "2_1") (pintype "bidirectional"))
      (node (ref "Q6") (pin "3") (pinfunction "D_3") (pintype "passive"))
      (node (ref "U1") (pin "50") (pinfunction "VBAT_50") (pintype "bidirectional"))
      (node (ref "U1") (pin "51") (pinfunction "VBAT_51") (pintype "bidirectional"))
    )
    (net (code "127") (name "VSYS") (class "Default")
      (node (ref "C15") (pin "2") (pinfunction "2_2") (pintype "passive"))
      (node (ref "C24") (pin "1") (pinfunction "1_1") (pintype "passive"))
      (node (ref "C28") (pin "2") (pinfunction "2_2") (pintype "passive"))
      (node (ref "D16") (pin "+") (pinfunction "+_+") (pintype "passive"))
      (node (ref "L3") (pin "2") (pinfunction "2_2") (pintype "passive"))
      (node (ref "Q6") (pin "2") (pinfunction "S_2") (pintype "passive"))
      (node (ref "R26") (pin "2") (pinfunction "2_2") (pintype "passive"))
      (node (ref "R61") (pin "2") (pinfunction "2_2") (pintype "passive"))
      (node (ref "TP6") (pin "T") (pinfunction "T_T") (pintype "bidirectional"))
      (node (ref "U3") (pin "5") (pinfunction "EN_5") (pintype "bidirectional"))
      (node (ref "U3") (pin "7") (pinfunction "AVIN_7") (pintype "bidirectional"))
      (node (ref "U3") (pin "8") (pinfunction "PVIN_8") (pintype "bidirectional"))
      (node (ref "U5") (pin "1") (pinfunction "SYS_1") (pintype "bidirectional"))
      (node (ref "U5") (pin "15") (pinfunction "SYS_15") (pintype "bidirectional"))
    )
    (net (code "128") (name "unconnected-(J1-Pad5)") (class "Default")
      (node (ref "J1") (pin "5") (pinfunction "5_5") (pintype "bidirectional"))
    )
    (net (code "129") (name "unconnected-(J1-Pad7)") (class "Default")
      (node (ref "J1") (pin "7") (pinfunction "7_7") (pintype "bidirectional"))
    )
    (net (code "130") (name "unconnected-(J1-Pad8)") (class "Default")
      (node (ref "J1") (pin "8") (pinfunction "8_8") (pintype "bidirectional"))
    )
    (net (code "131") (name "unconnected-(J9-ID-Pad4)") (class "Default")
      (node (ref "J9") (pin "4") (pinfunction "ID_4") (pintype "bidirectional"))
    )
    (net (code "132") (name "unconnected-(J11-DAT1-PadT8)") (class "Default")
      (node (ref "J11") (pin "T8") (pinfunction "DAT1_T8") (pintype "bidirectional"))
    )
    (net (code "133") (name "unconnected-(J11-DAT2-PadT1)") (class "Default")
      (node (ref "J11") (pin "T1") (pinfunction "DAT2_T1") (pintype "bidirectional"))
    )
    (net (code "134") (name "unconnected-(K1-A0-Pad1)") (class "Default")
      (node (ref "K1") (pin "1") (pinfunction "A0_1") (pintype "bidirectional"))
    )
    (net (code "135") (name "unconnected-(K1-B0-Pad3)") (class "Default")
      (node (ref "K1") (pin "3") (pinfunction "B0_3") (pintype "bidirectional"))
    )
    (net (code "136") (name "unconnected-(K2-A0-Pad1)") (class "Default")
      (node (ref "K2") (pin "1") (pinfunction "A0_1") (pintype "bidirectional"))
    )
    (net (code "137") (name "unconnected-(K2-B0-Pad3)") (class "Default")
      (node (ref "K2") (pin "3") (pinfunction "B0_3") (pintype "bidirectional"))
    )
    (net (code "138") (name "unconnected-(LED1-DOUT-Pad1)") (class "Default")
      (node (ref "LED1") (pin "1") (pinfunction "DOUT_1") (pintype "bidirectional"))
    )
    (net (code "139") (name "unconnected-(U1-1PPS-Pad17)") (class "Default")
      (node (ref "U1") (pin "17") (pinfunction "1PPS_17") (pintype "bidirectional"))
    )
    (net (code "140") (name "unconnected-(U1-ADC-Pad6)") (class "Default")
      (node (ref "U1") (pin "6") (pinfunction "ADC_6") (pintype "bidirectional"))
    )
    (net (code "141") (name "unconnected-(U1-CTS-Pad38)") (class "Default")
      (node (ref "U1") (pin "38") (pinfunction "CTS_38") (pintype "bidirectional"))
    )
    (net (code "142") (name "unconnected-(U1-DCD-Pad36)") (class "Default")
      (node (ref "U1") (pin "36") (pinfunction "DCD_36") (pintype "bidirectional"))
    )
    (net (code "143") (name "unconnected-(U1-PCM_CLK-Pad59)") (class "Default")
      (node (ref "U1") (pin "59") (pinfunction "PCM_CLK_59") (pintype "bidirectional"))
    )
    (net (code "144") (name "unconnected-(U1-PCM_IN-Pad62)") (class "Default")
      (node (ref "U1") (pin "62") (pinfunction "PCM_IN_62") (pintype "bidirectional"))
    )
    (net (code "145") (name "unconnected-(U1-PCM_OUT-Pad60)") (class "Default")
      (node (ref "U1") (pin "60") (pinfunction "PCM_OUT_60") (pintype "bidirectional"))
    )
    (net (code "146") (name "unconnected-(U1-PCM_SYNC-Pad61)") (class "Default")
      (node (ref "U1") (pin "61") (pinfunction "PCM_SYNC_61") (pintype "bidirectional"))
    )
    (net (code "147") (name "unconnected-(U1-RESERVED-Pad46)") (class "Default")
      (node (ref "U1") (pin "46") (pinfunction "RESERVED_46") (pintype "bidirectional"))
    )
    (net (code "148") (name "unconnected-(U1-RESERVED-Pad55)") (class "Default")
      (node (ref "U1") (pin "55") (pinfunction "RESERVED_55") (pintype "bidirectional"))
    )
    (net (code "149") (name "unconnected-(U1-RESERVED-Pad56)") (class "Default")
      (node (ref "U1") (pin "56") (pinfunction "RESERVED_56") (pintype "bidirectional"))
    )
    (net (code "150") (name "unconnected-(U1-RESERVED-Pad57)") (class "Default")
      (node (ref "U1") (pin "57") (pinfunction "RESERVED_57") (pintype "bidirectional"))
    )
    (net (code "151") (name "unconnected-(U1-RESERVED-Pad58)") (class "Default")
      (node (ref "U1") (pin "58") (pinfunction "RESERVED_58") (pintype "bidirectional"))
    )
    (net (code "152") (name "unconnected-(U1-RESERVED-Pad63)") (class "Default")
      (node (ref "U1") (pin "63") (pinfunction "RESERVED_63") (pintype "bidirectional"))
    )
    (net (code "153") (name "unconnected-(U1-RESERVED-Pad64)") (class "Default")
      (node (ref "U1") (pin "64") (pinfunction "RESERVED_64") (pintype "bidirectional"))
    )
    (net (code "154") (name "unconnected-(U1-RESERVED-Pad65)") (class "Default")
      (node (ref "U1") (pin "65") (pinfunction "RESERVED_65") (pintype "bidirectional"))
    )
    (net (code "155") (name "unconnected-(U1-RESERVED-Pad66)") (class "Default")
      (node (ref "U1") (pin "66") (pinfunction "RESERVED_66") (pintype "bidirectional"))
    )
    (net (code "156") (name "unconnected-(U1-RESERVED-Pad67)") (class "Default")
      (node (ref "U1") (pin "67") (pinfunction "RESERVED_67") (pintype "bidirectional"))
    )
    (net (code "157") (name "unconnected-(U1-RESERVED-Pad68)") (class "Default")
      (node (ref "U1") (pin "68") (pinfunction "RESERVED_68") (pintype "bidirectional"))
    )
    (net (code "158") (name "unconnected-(U1-RI-Pad35)") (class "Default")
      (node (ref "U1") (pin "35") (pinfunction "RI_35") (pintype "bidirectional"))
    )
    (net (code "159") (name "unconnected-(U1-RTS-Pad39)") (class "Default")
      (node (ref "U1") (pin "39") (pinfunction "RTS_39") (pintype "bidirectional"))
    )
    (net (code "160") (name "unconnected-(U1-SIM2_CLK-Pad10)") (class "Default")
      (node (ref "U1") (pin "10") (pinfunction "SIM2_CLK_10") (pintype "bidirectional"))
    )
    (net (code "161") (name "unconnected-(U1-SIM2_DATA-Pad11)") (class "Default")
      (node (ref "U1") (pin "11") (pinfunction "SIM2_DATA_11") (pintype "bidirectional"))
    )
    (net (code "162") (name "unconnected-(U1-SIM2_RST-Pad12)") (class "Default")
      (node (ref "U1") (pin "12") (pinfunction "SIM2_RST_12") (pintype "bidirectional"))
    )
    (net (code "163") (name "unconnected-(U1-SIM2_VDD-Pad13)") (class "Default")
      (node (ref "U1") (pin "13") (pinfunction "SIM2_VDD_13") (pintype "bidirectional"))
    )
    (net (code "164") (name "unconnected-(U1-VDD_EXT-Pad43)") (class "Default")
      (node (ref "U1") (pin "43") (pinfunction "VDD_EXT_43") (pintype "bidirectional"))
    )
    (net (code "165") (name "unconnected-(U4-PA13{slash}I2C{slash}EIC{slash}SCOM2PAD1+{slash}TC2-Pad22)") (class "Default")
      (node (ref "U4") (pin "22") (pinfunction "PA13/I2C/EIC/SCOM2PAD1+/TC2_22") (pintype "bidirectional"))
    )
    (net (code "166") (name "unconnected-(U4-PA28{slash}EIC-Pad41)") (class "Default")
      (node (ref "U4") (pin "41") (pinfunction "PA28/EIC_41") (pintype "bidirectional"))
    )
  )
)
